# MAIN.net
KiCad netlist of a schematic drawn in Altium Designer
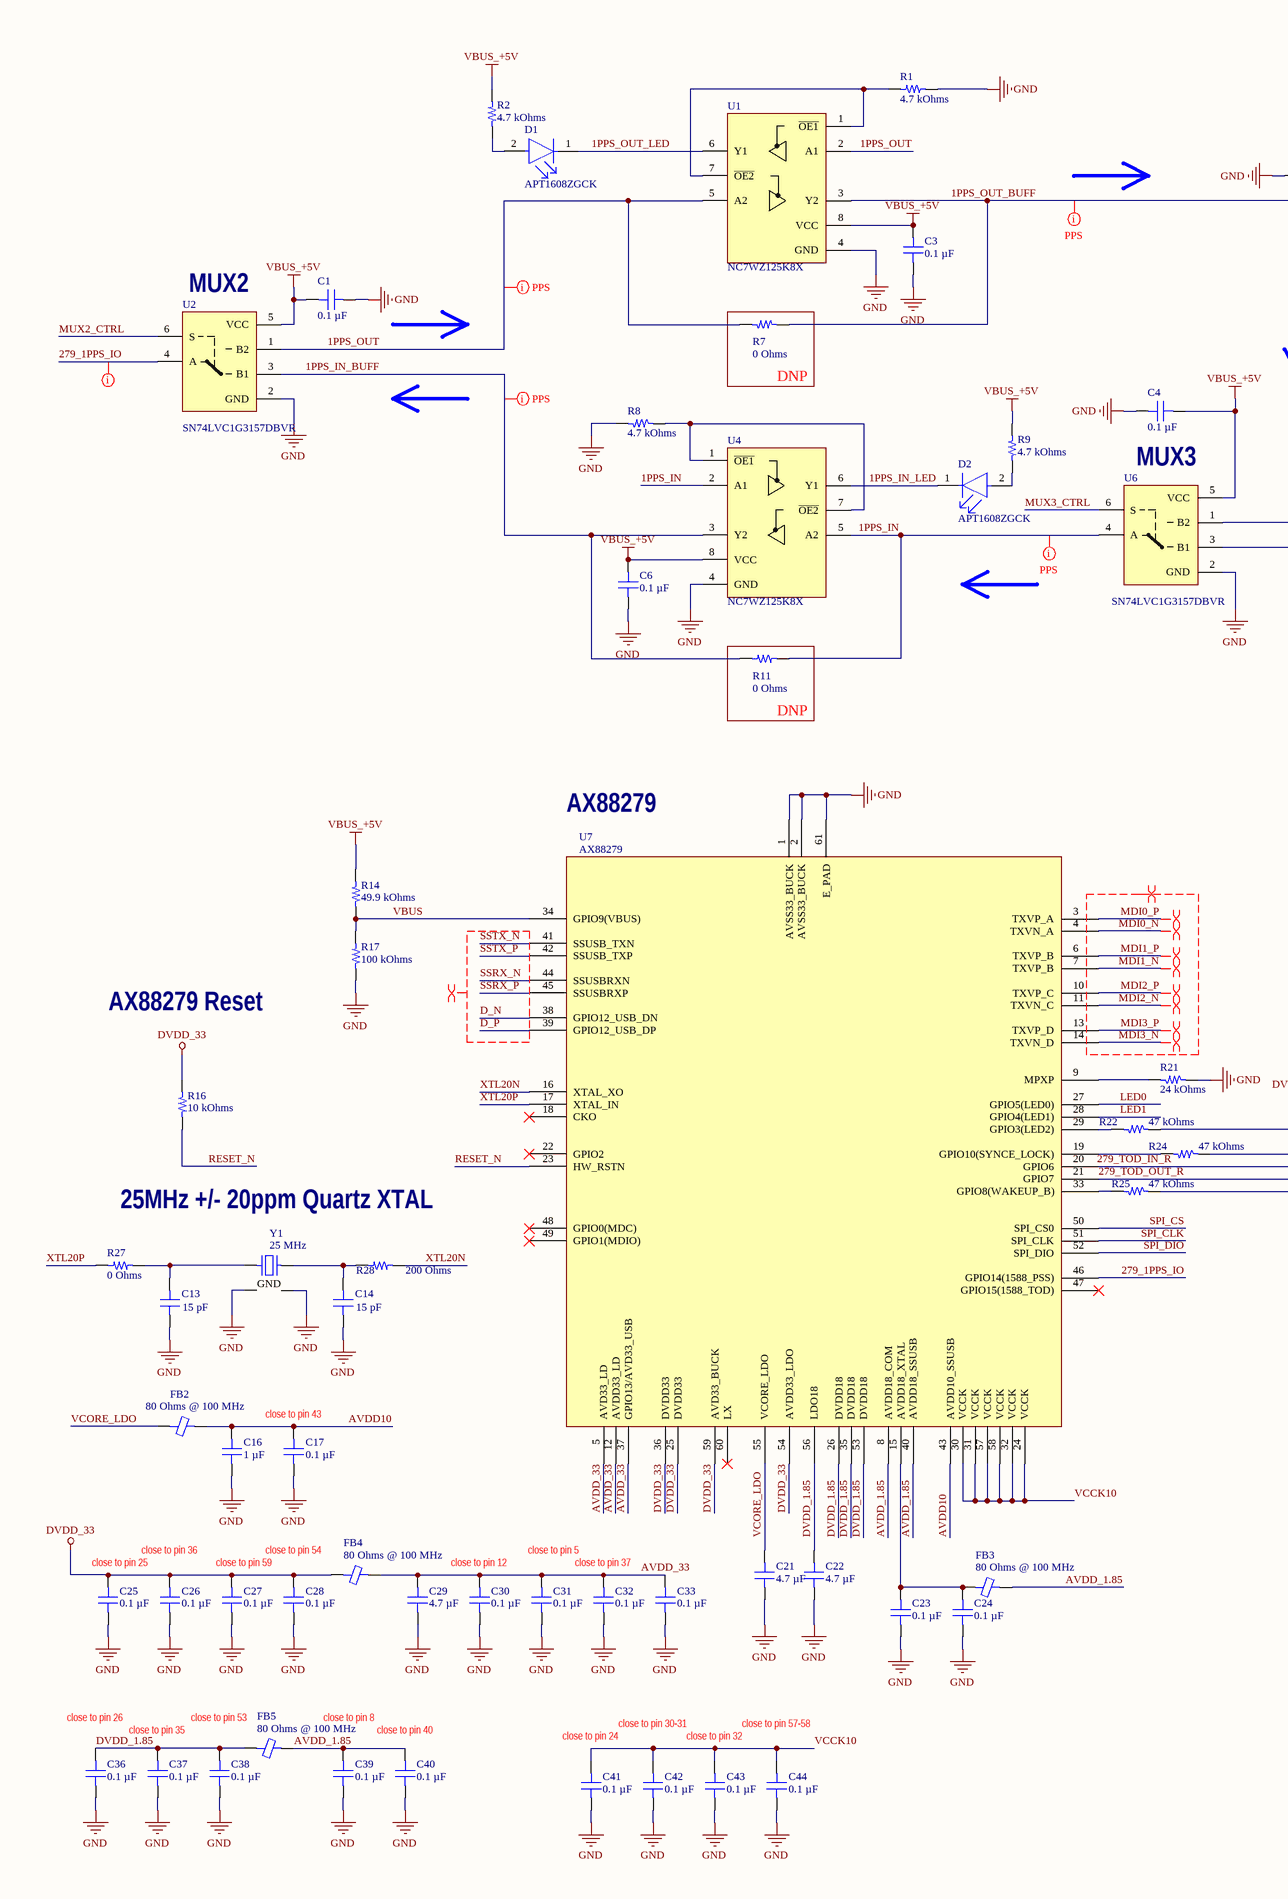
[diagram p0: MAIN.SchDoc, left]
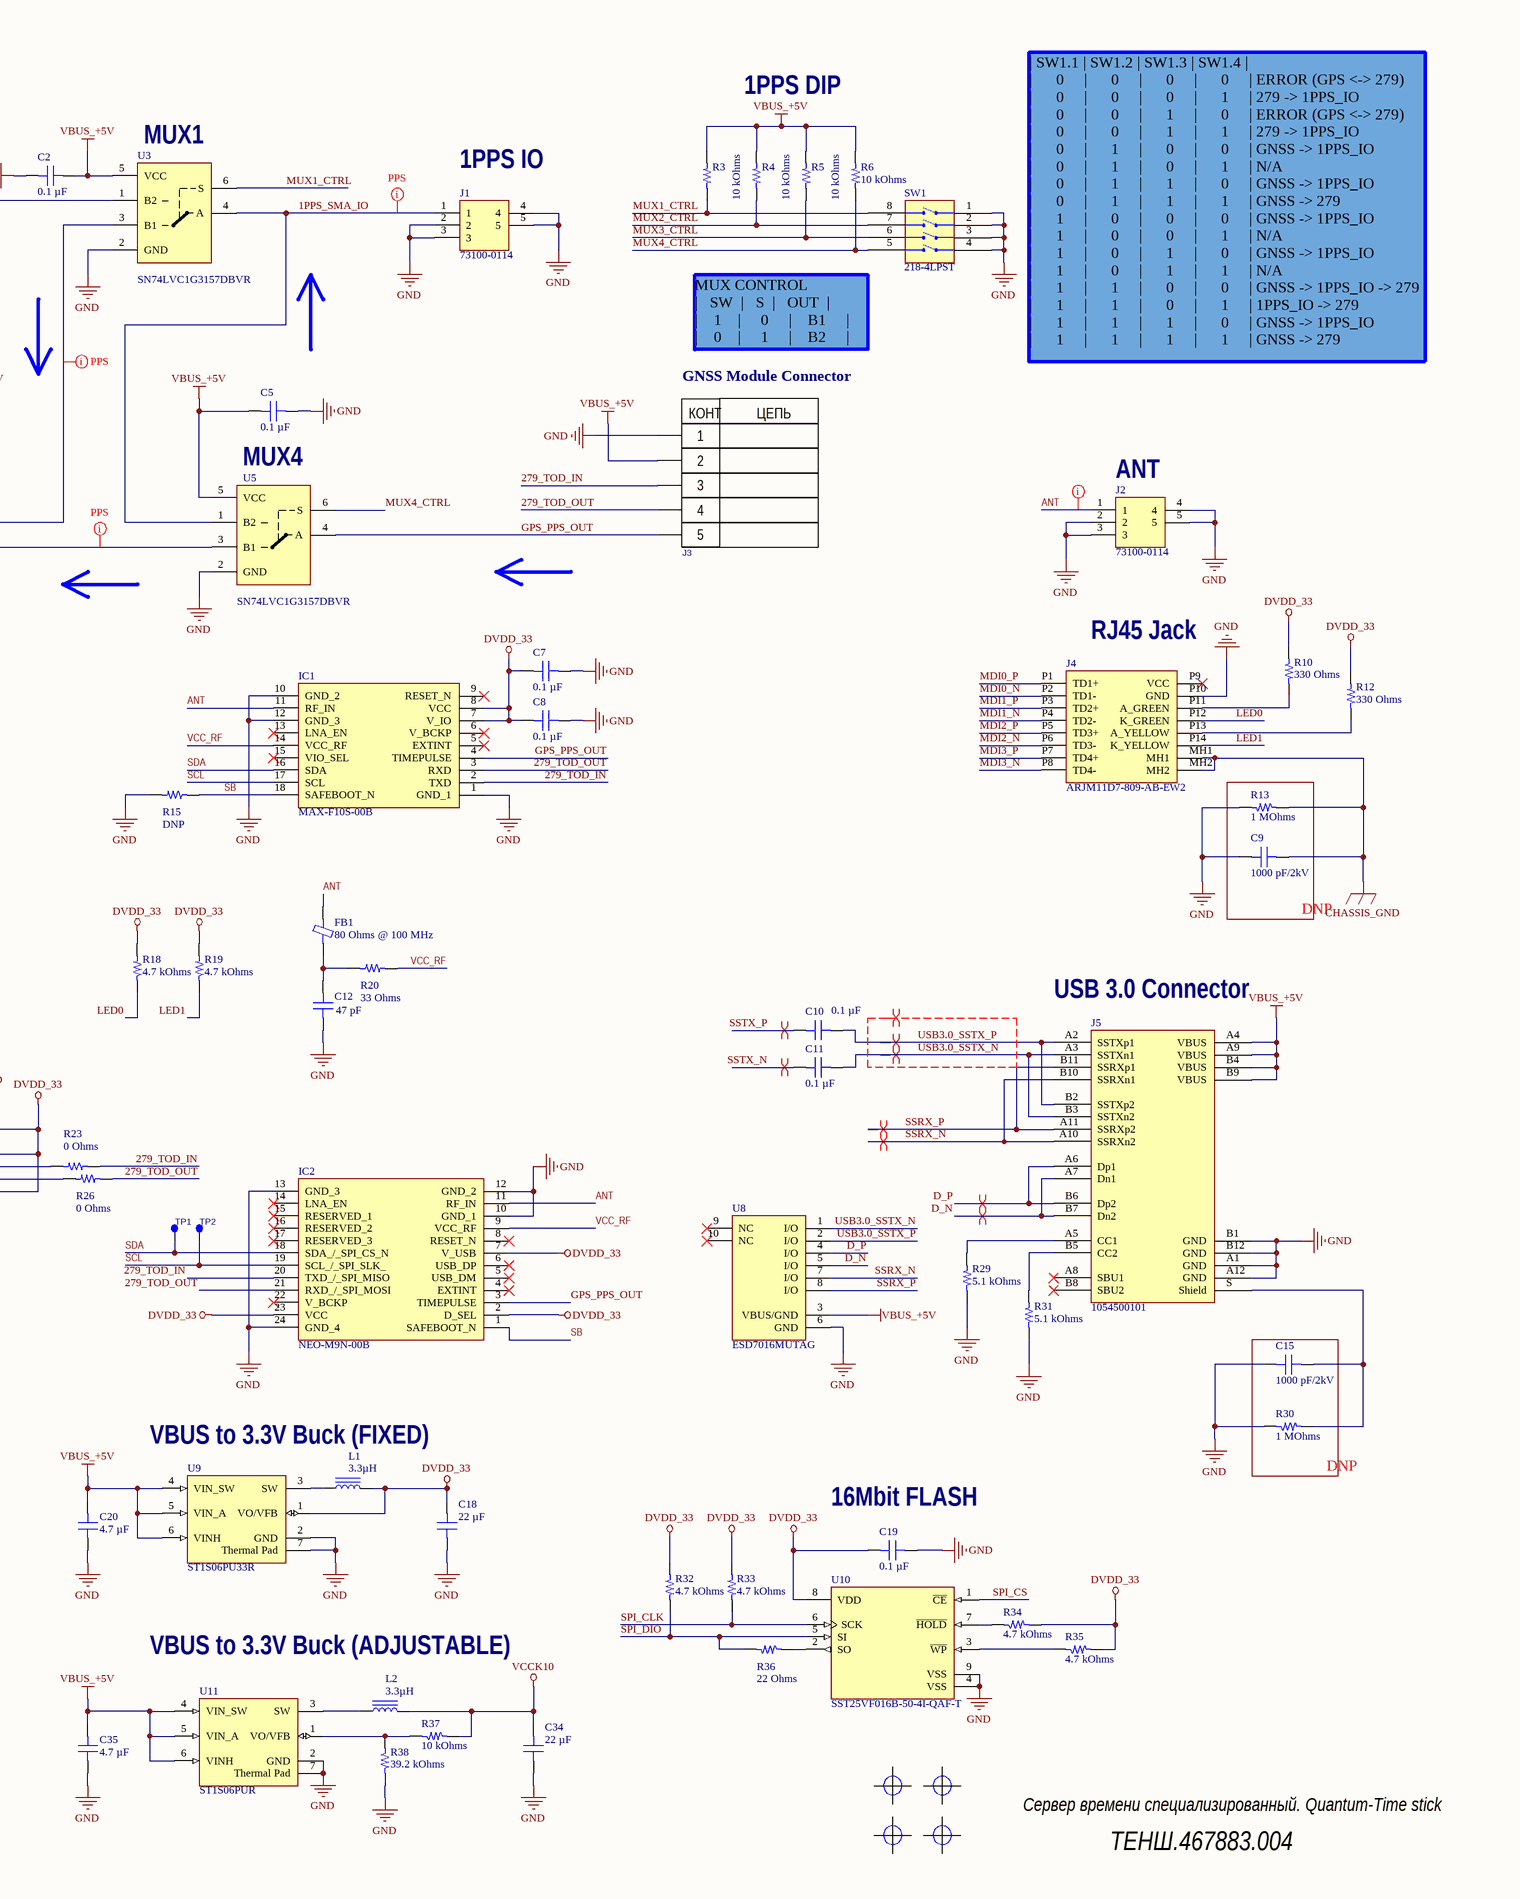
[diagram p1: MAIN.SchDoc, right]

(export (version "E")
  (design (tool "Eeschema 10.0.6"))
  (components
    (comp (ref "C1")
      (value "0.1 µF")
      (footprint "CAP 0402_1005")
      (description "CAP CER 0.1UF 10V X7R 0402")
      (fields (field (name "TOLERANCE") "±10%") (field (name "MANUFACTURER") "Yageo"))
      (libsource (lib "Celestial Altium Library - altium_library") (part "Capacitor"))
    )
    (comp (ref "C2")
      (value "0.1 µF")
      (footprint "CAP 0402_1005")
      (description "CAP CER 0.1UF 10V X7R 0402")
      (fields (field (name "TOLERANCE") "±10%") (field (name "MANUFACTURER") "Yageo"))
      (libsource (lib "Celestial Altium Library - altium_library") (part "Capacitor"))
    )
    (comp (ref "C3")
      (value "0.1 µF")
      (footprint "CAP 0402_1005")
      (description "CAP CER 0.1UF 10V X7R 0402")
      (fields (field (name "TOLERANCE") "±10%") (field (name "MANUFACTURER") "Yageo"))
      (libsource (lib "Celestial Altium Library - altium_library") (part "Capacitor"))
    )
    (comp (ref "C4")
      (value "0.1 µF")
      (footprint "CAP 0402_1005")
      (description "CAP CER 0.1UF 10V X7R 0402")
      (fields (field (name "TOLERANCE") "±10%") (field (name "MANUFACTURER") "Yageo"))
      (libsource (lib "Celestial Altium Library - altium_library") (part "Capacitor"))
    )
    (comp (ref "C5")
      (value "0.1 µF")
      (footprint "CAP 0402_1005")
      (description "CAP CER 0.1UF 10V X7R 0402")
      (fields (field (name "TOLERANCE") "±10%") (field (name "MANUFACTURER") "Yageo"))
      (libsource (lib "Celestial Altium Library - altium_library") (part "Capacitor"))
    )
    (comp (ref "C6")
      (value "0.1 µF")
      (footprint "CAP 0402_1005")
      (description "CAP CER 0.1UF 10V X7R 0402")
      (fields (field (name "TOLERANCE") "±10%") (field (name "MANUFACTURER") "Yageo"))
      (libsource (lib "Celestial Altium Library - altium_library") (part "Capacitor"))
    )
    (comp (ref "C7")
      (value "0.1 µF")
      (footprint "CAP 0402_1005")
      (description "CAP CER 0.1UF 10V X7R 0402")
      (fields (field (name "TOLERANCE") "±10%") (field (name "MANUFACTURER") "Yageo"))
      (libsource (lib "Celestial Altium Library - altium_library") (part "Capacitor"))
    )
    (comp (ref "C8")
      (value "0.1 µF")
      (footprint "CAP 0402_1005")
      (description "CAP CER 0.1UF 10V X7R 0402")
      (fields (field (name "TOLERANCE") "±10%") (field (name "MANUFACTURER") "Yageo"))
      (libsource (lib "Celestial Altium Library - altium_library") (part "Capacitor"))
    )
    (comp (ref "C9")
      (value "1000 pF/2kV")
      (footprint "CAP 1206_3216 - 0.8MM")
      (description "CAP CER 1000PF 2KV X7R 1206")
      (fields (field (name "PART NUMBER") "CC1206KKX7RDBB102") (field (name "MANUFACTURER") "Yageo"))
      (libsource (lib "Celestial Altium Library - altium_library") (part "Capacitor"))
    )
    (comp (ref "C10")
      (value "0.1 µF")
      (footprint "CAP 0402_1005")
      (description "CAP CER 0.1UF 10V X7R 0402")
      (fields (field (name "TOLERANCE") "±10%") (field (name "MANUFACTURER") "Yageo"))
      (libsource (lib "Celestial Altium Library - altium_library") (part "Capacitor"))
    )
    (comp (ref "C11")
      (value "0.1 µF")
      (footprint "CAP 0402_1005")
      (description "CAP CER 0.1UF 10V X7R 0402")
      (fields (field (name "TOLERANCE") "±10%") (field (name "MANUFACTURER") "Yageo"))
      (libsource (lib "Celestial Altium Library - altium_library") (part "Capacitor"))
    )
    (comp (ref "C12")
      (value "47 pF")
      (footprint "CAP 0402_1005")
      (description "CAP CER 47PF 50V C0G/NPO 0402")
      (fields (field (name "MANUFACTURER") "Yageo") (field (name "TOLERANCE") "±10%"))
      (libsource (lib "Celestial Altium Library - altium_library") (part "Capacitor"))
    )
    (comp (ref "C13")
      (value "15 pF")
      (footprint "CAP 0402_1005")
      (description "CAP CER 15PF 50V C0G/NPO 0402")
      (fields (field (name "MANUFACTURER") "Yageo") (field (name "TOLERANCE") "±10%"))
      (libsource (lib "Celestial Altium Library - altium_library") (part "Capacitor"))
    )
    (comp (ref "C14")
      (value "15 pF")
      (footprint "CAP 0402_1005")
      (description "CAP CER 15PF 50V C0G/NPO 0402")
      (fields (field (name "MANUFACTURER") "Yageo") (field (name "TOLERANCE") "±10%"))
      (libsource (lib "Celestial Altium Library - altium_library") (part "Capacitor"))
    )
    (comp (ref "C15")
      (value "1000 pF/2kV")
      (footprint "CAP 1206_3216 - 0.8MM")
      (description "CAP CER 1000PF 2KV X7R 1206")
      (fields (field (name "PART NUMBER") "CC1206KKX7RDBB102") (field (name "MANUFACTURER") "Yageo"))
      (libsource (lib "Celestial Altium Library - altium_library") (part "Capacitor"))
    )
    (comp (ref "C16")
      (value "1 µF")
      (footprint "CAP 0402_1005")
      (description "CAP CER 1UF 10V X5R 0402")
      (fields (field (name "TOLERANCE") "±10%") (field (name "MANUFACTURER") "Yageo"))
      (libsource (lib "Celestial Altium Library - altium_library") (part "Capacitor"))
    )
    (comp (ref "C17")
      (value "0.1 µF")
      (footprint "CAP 0402_1005")
      (description "CAP CER 0.1UF 10V X7R 0402")
      (fields (field (name "TOLERANCE") "±10%") (field (name "MANUFACTURER") "Yageo"))
      (libsource (lib "Celestial Altium Library - altium_library") (part "Capacitor"))
    )
    (comp (ref "C18")
      (value "22 µF")
      (footprint "CAP 0603_1608")
      (description "CAP CER 22UF 10V X5R 0603")
      (fields (field (name "MANUFACTURER") "Yageo") (field (name "TOLERANCE") "±20%"))
      (libsource (lib "Celestial Altium Library - altium_library") (part "Capacitor"))
    )
    (comp (ref "C19")
      (value "0.1 µF")
      (footprint "CAP 0402_1005")
      (description "CAP CER 0.1UF 10V X7R 0402")
      (fields (field (name "TOLERANCE") "±10%") (field (name "MANUFACTURER") "Yageo"))
      (libsource (lib "Celestial Altium Library - altium_library") (part "Capacitor"))
    )
    (comp (ref "C20")
      (value "4.7 µF")
      (footprint "CAP 0402_1005")
      (description "CAP CER 4.7UF 10V X5R 0402")
      (fields (field (name "TOLERANCE") "±20%") (field (name "MANUFACTURER") "Yageo"))
      (libsource (lib "Celestial Altium Library - altium_library") (part "Capacitor"))
    )
    (comp (ref "C21")
      (value "4.7 µF")
      (footprint "CAP 0402_1005")
      (description "CAP CER 4.7UF 10V X5R 0402")
      (fields (field (name "TOLERANCE") "±20%") (field (name "MANUFACTURER") "Yageo"))
      (libsource (lib "Celestial Altium Library - altium_library") (part "Capacitor"))
    )
    (comp (ref "C22")
      (value "4.7 µF")
      (footprint "CAP 0402_1005")
      (description "CAP CER 4.7UF 10V X5R 0402")
      (fields (field (name "TOLERANCE") "±20%") (field (name "MANUFACTURER") "Yageo"))
      (libsource (lib "Celestial Altium Library - altium_library") (part "Capacitor"))
    )
    (comp (ref "C23")
      (value "0.1 µF")
      (footprint "CAP 0402_1005")
      (description "CAP CER 0.1UF 10V X7R 0402")
      (fields (field (name "TOLERANCE") "±10%") (field (name "MANUFACTURER") "Yageo"))
      (libsource (lib "Celestial Altium Library - altium_library") (part "Capacitor"))
    )
    (comp (ref "C24")
      (value "0.1 µF")
      (footprint "CAP 0402_1005")
      (description "CAP CER 0.1UF 10V X7R 0402")
      (fields (field (name "TOLERANCE") "±10%") (field (name "MANUFACTURER") "Yageo"))
      (libsource (lib "Celestial Altium Library - altium_library") (part "Capacitor"))
    )
    (comp (ref "C25")
      (value "0.1 µF")
      (footprint "CAP 0402_1005")
      (description "CAP CER 0.1UF 10V X7R 0402")
      (fields (field (name "TOLERANCE") "±10%") (field (name "MANUFACTURER") "Yageo"))
      (libsource (lib "Celestial Altium Library - altium_library") (part "Capacitor"))
    )
    (comp (ref "C26")
      (value "0.1 µF")
      (footprint "CAP 0402_1005")
      (description "CAP CER 0.1UF 10V X7R 0402")
      (fields (field (name "TOLERANCE") "±10%") (field (name "MANUFACTURER") "Yageo"))
      (libsource (lib "Celestial Altium Library - altium_library") (part "Capacitor"))
    )
    (comp (ref "C27")
      (value "0.1 µF")
      (footprint "CAP 0402_1005")
      (description "CAP CER 0.1UF 10V X7R 0402")
      (fields (field (name "TOLERANCE") "±10%") (field (name "MANUFACTURER") "Yageo"))
      (libsource (lib "Celestial Altium Library - altium_library") (part "Capacitor"))
    )
    (comp (ref "C28")
      (value "0.1 µF")
      (footprint "CAP 0402_1005")
      (description "CAP CER 0.1UF 10V X7R 0402")
      (fields (field (name "TOLERANCE") "±10%") (field (name "MANUFACTURER") "Yageo"))
      (libsource (lib "Celestial Altium Library - altium_library") (part "Capacitor"))
    )
    (comp (ref "C29")
      (value "4.7 µF")
      (footprint "CAP 0402_1005")
      (description "CAP CER 4.7UF 10V X5R 0402")
      (fields (field (name "TOLERANCE") "±20%") (field (name "MANUFACTURER") "Yageo"))
      (libsource (lib "Celestial Altium Library - altium_library") (part "Capacitor"))
    )
    (comp (ref "C30")
      (value "0.1 µF")
      (footprint "CAP 0402_1005")
      (description "CAP CER 0.1UF 10V X7R 0402")
      (fields (field (name "TOLERANCE") "±10%") (field (name "MANUFACTURER") "Yageo"))
      (libsource (lib "Celestial Altium Library - altium_library") (part "Capacitor"))
    )
    (comp (ref "C31")
      (value "0.1 µF")
      (footprint "CAP 0402_1005")
      (description "CAP CER 0.1UF 10V X7R 0402")
      (fields (field (name "TOLERANCE") "±10%") (field (name "MANUFACTURER") "Yageo"))
      (libsource (lib "Celestial Altium Library - altium_library") (part "Capacitor"))
    )
    (comp (ref "C32")
      (value "0.1 µF")
      (footprint "CAP 0402_1005")
      (description "CAP CER 0.1UF 10V X7R 0402")
      (fields (field (name "TOLERANCE") "±10%") (field (name "MANUFACTURER") "Yageo"))
      (libsource (lib "Celestial Altium Library - altium_library") (part "Capacitor"))
    )
    (comp (ref "C33")
      (value "0.1 µF")
      (footprint "CAP 0402_1005")
      (description "CAP CER 0.1UF 10V X7R 0402")
      (fields (field (name "TOLERANCE") "±10%") (field (name "MANUFACTURER") "Yageo"))
      (libsource (lib "Celestial Altium Library - altium_library") (part "Capacitor"))
    )
    (comp (ref "C34")
      (value "22 µF")
      (footprint "CAP 0603_1608")
      (description "CAP CER 22UF 10V X5R 0603")
      (fields (field (name "MANUFACTURER") "Yageo") (field (name "TOLERANCE") "±20%"))
      (libsource (lib "Celestial Altium Library - altium_library") (part "Capacitor"))
    )
    (comp (ref "C35")
      (value "4.7 µF")
      (footprint "CAP 0402_1005")
      (description "CAP CER 4.7UF 10V X5R 0402")
      (fields (field (name "TOLERANCE") "±20%") (field (name "MANUFACTURER") "Yageo"))
      (libsource (lib "Celestial Altium Library - altium_library") (part "Capacitor"))
    )
    (comp (ref "C36")
      (value "0.1 µF")
      (footprint "CAP 0402_1005")
      (description "CAP CER 0.1UF 10V X7R 0402")
      (fields (field (name "TOLERANCE") "±10%") (field (name "MANUFACTURER") "Yageo"))
      (libsource (lib "Celestial Altium Library - altium_library") (part "Capacitor"))
    )
    (comp (ref "C37")
      (value "0.1 µF")
      (footprint "CAP 0402_1005")
      (description "CAP CER 0.1UF 10V X7R 0402")
      (fields (field (name "TOLERANCE") "±10%") (field (name "MANUFACTURER") "Yageo"))
      (libsource (lib "Celestial Altium Library - altium_library") (part "Capacitor"))
    )
    (comp (ref "C38")
      (value "0.1 µF")
      (footprint "CAP 0402_1005")
      (description "CAP CER 0.1UF 10V X7R 0402")
      (fields (field (name "TOLERANCE") "±10%") (field (name "MANUFACTURER") "Yageo"))
      (libsource (lib "Celestial Altium Library - altium_library") (part "Capacitor"))
    )
    (comp (ref "C39")
      (value "0.1 µF")
      (footprint "CAP 0402_1005")
      (description "CAP CER 0.1UF 10V X7R 0402")
      (fields (field (name "TOLERANCE") "±10%") (field (name "MANUFACTURER") "Yageo"))
      (libsource (lib "Celestial Altium Library - altium_library") (part "Capacitor"))
    )
    (comp (ref "C40")
      (value "0.1 µF")
      (footprint "CAP 0402_1005")
      (description "CAP CER 0.1UF 10V X7R 0402")
      (fields (field (name "TOLERANCE") "±10%") (field (name "MANUFACTURER") "Yageo"))
      (libsource (lib "Celestial Altium Library - altium_library") (part "Capacitor"))
    )
    (comp (ref "C41")
      (value "0.1 µF")
      (footprint "CAP 0402_1005")
      (description "CAP CER 0.1UF 10V X7R 0402")
      (fields (field (name "TOLERANCE") "±10%") (field (name "MANUFACTURER") "Yageo"))
      (libsource (lib "Celestial Altium Library - altium_library") (part "Capacitor"))
    )
    (comp (ref "C42")
      (value "0.1 µF")
      (footprint "CAP 0402_1005")
      (description "CAP CER 0.1UF 10V X7R 0402")
      (fields (field (name "TOLERANCE") "±10%") (field (name "MANUFACTURER") "Yageo"))
      (libsource (lib "Celestial Altium Library - altium_library") (part "Capacitor"))
    )
    (comp (ref "C43")
      (value "0.1 µF")
      (footprint "CAP 0402_1005")
      (description "CAP CER 0.1UF 10V X7R 0402")
      (fields (field (name "TOLERANCE") "±10%") (field (name "MANUFACTURER") "Yageo"))
      (libsource (lib "Celestial Altium Library - altium_library") (part "Capacitor"))
    )
    (comp (ref "C44")
      (value "0.1 µF")
      (footprint "CAP 0402_1005")
      (description "CAP CER 0.1UF 10V X7R 0402")
      (fields (field (name "TOLERANCE") "±10%") (field (name "MANUFACTURER") "Yageo"))
      (libsource (lib "Celestial Altium Library - altium_library") (part "Capacitor"))
    )
    (comp (ref "D1")
      (value "APT1608ZGCK")
      (footprint "FP-APT1608ZGCK-MFG")
      (description "LED GREEN CLEAR CHIP SMD")
      (fields (field (name "MANUFACTURER") "Kingbright"))
      (libsource (lib "Altium Content Vault") (part "8706943c75ba83719d021d2fdc84c58"))
    )
    (comp (ref "D2")
      (value "APT1608ZGCK")
      (footprint "FP-APT1608ZGCK-MFG")
      (description "LED GREEN CLEAR CHIP SMD")
      (fields (field (name "MANUFACTURER") "Kingbright"))
      (libsource (lib "Altium Content Vault") (part "8706943c75ba83719d021d2fdc84c58"))
    )
    (comp (ref "FB1")
      (value "80 Ohms @ 100 MHz")
      (footprint "FER 0402_1005")
      (description "FERRITE BEAD 80 OHM 0402 1LN")
      (fields
        (field (name "MANUFACTURER") "Murata Electronics")
        (field (name "PART NUMBER") "BLM15PD800SN1D")
      )
      (libsource (lib "Celestial Altium Library - altium_library") (part "Ferrite Chip"))
    )
    (comp (ref "FB2")
      (value "80 Ohms @ 100 MHz")
      (footprint "FER 0402_1005")
      (description "FERRITE BEAD 80 OHM 0402 1LN")
      (fields
        (field (name "MANUFACTURER") "Murata Electronics")
        (field (name "PART NUMBER") "BLM15PD800SN1D")
      )
      (libsource (lib "Celestial Altium Library - altium_library") (part "Ferrite Chip"))
    )
    (comp (ref "FB3")
      (value "80 Ohms @ 100 MHz")
      (footprint "FER 0402_1005")
      (description "FERRITE BEAD 80 OHM 0402 1LN")
      (fields
        (field (name "MANUFACTURER") "Murata Electronics")
        (field (name "PART NUMBER") "BLM15PD800SN1D")
      )
      (libsource (lib "Celestial Altium Library - altium_library") (part "Ferrite Chip"))
    )
    (comp (ref "FB4")
      (value "80 Ohms @ 100 MHz")
      (footprint "FER 0402_1005")
      (description "FERRITE BEAD 80 OHM 0402 1LN")
      (fields
        (field (name "MANUFACTURER") "Murata Electronics")
        (field (name "PART NUMBER") "BLM15PD800SN1D")
      )
      (libsource (lib "Celestial Altium Library - altium_library") (part "Ferrite Chip"))
    )
    (comp (ref "FB5")
      (value "80 Ohms @ 100 MHz")
      (footprint "FER 0402_1005")
      (description "FERRITE BEAD 80 OHM 0402 1LN")
      (fields
        (field (name "MANUFACTURER") "Murata Electronics")
        (field (name "PART NUMBER") "BLM15PD800SN1D")
      )
      (libsource (lib "Celestial Altium Library - altium_library") (part "Ferrite Chip"))
    )
    (comp (ref "IC1")
      (value "MAX-F10S-00B")
      (footprint "SamacSys:MAXF10S00B")
      (description "Integrated Circuit")
      (libsource (lib "SamacSys") (part "MAX-F10S-00B"))
    )
    (comp (ref "IC2")
      (value "NEO-M9N-00B")
      (footprint "SamacSys:NEOM9N00B")
      (description "Integrated Circuit")
      (fields (field (name "MOUSER PART NUMBER") "377-NEO-M9N-00B"))
      (libsource (lib "SamacSys") (part "NEO-M9N-00B"))
    )
    (comp (ref "J1")
      (value "73100-0114")
      (footprint "SamacSys:731000114")
      (description "Connector")
      (fields (field (name "MOUSER PART NUMBER") "538-73100-0114"))
      (libsource (lib "SamacSys") (part "73100-0114"))
    )
    (comp (ref "J2")
      (value "73100-0114")
      (footprint "SamacSys:731000114")
      (description "Connector")
      (fields (field (name "MOUSER PART NUMBER") "538-73100-0114"))
      (libsource (lib "SamacSys") (part "73100-0114"))
    )
    (comp (ref "J3")
      (value "PBS-5")
      (footprint "SamacSys:PBS-5")
      (description "Connector")
      (fields (field (name "MANUFACTURER") "Connfly") (field (name "PART NUMBER") "PBD-5"))
      (libsource (lib "SamacSys") (part "PBS-5"))
    )
    (comp (ref "J4")
      (value "ARJM11D7-809-AB-EW2")
      (footprint "SamacSys:ARJM11D7809ABEW2")
      (description "Connector")
      (fields (field (name "MOUSER PART NUMBER") "815-RJM11D7809ABEW2"))
      (libsource (lib "*") (part "ARJM11D7-809-AB-EW2"))
    )
    (comp (ref "J5")
      (value "1054500101")
      (footprint "Molex 1054500101")
      (description "CONN RCP USB3.1 TYPEC 24P SMD RA")
      (fields (field (name "MANUFACTURER") "Molex"))
      (libsource (lib "Celestial Altium Library - altium_library") (part "USB 3.0 Type C"))
    )
    (comp (ref "L1")
      (value "3.3µH")
      (footprint "IND 1008_2520")
      (description "FIXED IND 3.3UH 1.2A 100 MOHM")
      (fields (field (name "TOLERANCE") "±20%") (field (name "MANUFACTURER") "Murata Electronics"))
      (libsource (lib "Celestial Altium Library - altium_library") (part "Inductor"))
    )
    (comp (ref "L2")
      (value "3.3µH")
      (footprint "IND 1008_2520")
      (description "FIXED IND 3.3UH 1.2A 100 MOHM")
      (fields (field (name "TOLERANCE") "±20%") (field (name "MANUFACTURER") "Murata Electronics"))
      (libsource (lib "Celestial Altium Library - altium_library") (part "Inductor"))
    )
    (comp (ref "MNT1")
      (value "MOUNT_HOLE")
      (footprint "SamacSys:MOUNT_3mm")
      (description "Mount hole")
      (libsource (lib "SamacSys") (part "MOUNT_HOLE"))
    )
    (comp (ref "MNT2")
      (value "MOUNT_HOLE")
      (footprint "SamacSys:MOUNT_3mm")
      (description "Mount hole")
      (libsource (lib "SamacSys") (part "MOUNT_HOLE"))
    )
    (comp (ref "MNT3")
      (value "MOUNT_HOLE")
      (footprint "SamacSys:MOUNT_3mm")
      (description "Mount hole")
      (libsource (lib "SamacSys") (part "MOUNT_HOLE"))
    )
    (comp (ref "MNT4")
      (value "MOUNT_HOLE")
      (footprint "SamacSys:MOUNT_3mm")
      (description "Mount hole")
      (libsource (lib "SamacSys") (part "MOUNT_HOLE"))
    )
    (comp (ref "R1")
      (value "4.7 kOhms")
      (footprint "YAGEO RES 0402_1005")
      (description "RES 4.7K OHM 1% 1/16W 0402")
      (fields (field (name "TOLERANCE") "±1%") (field (name "MANUFACTURER") "Yageo"))
      (libsource (lib "Celestial Altium Library - altium_library") (part "Resistor"))
    )
    (comp (ref "R2")
      (value "4.7 kOhms")
      (footprint "YAGEO RES 0402_1005")
      (description "RES 4.7K OHM 1% 1/16W 0402")
      (fields (field (name "TOLERANCE") "±1%") (field (name "MANUFACTURER") "Yageo"))
      (libsource (lib "Celestial Altium Library - altium_library") (part "Resistor"))
    )
    (comp (ref "R3")
      (value "10 kOhms")
      (footprint "YAGEO RES 0402_1005")
      (description "RES 10K OHM 1% 1/16W 0402")
      (fields (field (name "TOLERANCE") "±1%") (field (name "MANUFACTURER") "Yageo"))
      (libsource (lib "Celestial Altium Library - altium_library") (part "Resistor"))
    )
    (comp (ref "R4")
      (value "10 kOhms")
      (footprint "YAGEO RES 0402_1005")
      (description "RES 10K OHM 1% 1/16W 0402")
      (fields (field (name "TOLERANCE") "±1%") (field (name "MANUFACTURER") "Yageo"))
      (libsource (lib "Celestial Altium Library - altium_library") (part "Resistor"))
    )
    (comp (ref "R5")
      (value "10 kOhms")
      (footprint "YAGEO RES 0402_1005")
      (description "RES 10K OHM 1% 1/16W 0402")
      (fields (field (name "TOLERANCE") "±1%") (field (name "MANUFACTURER") "Yageo"))
      (libsource (lib "Celestial Altium Library - altium_library") (part "Resistor"))
    )
    (comp (ref "R6")
      (value "10 kOhms")
      (footprint "YAGEO RES 0402_1005")
      (description "RES 10K OHM 1% 1/16W 0402")
      (fields (field (name "TOLERANCE") "±1%") (field (name "MANUFACTURER") "Yageo"))
      (libsource (lib "Celestial Altium Library - altium_library") (part "Resistor"))
    )
    (comp (ref "R7")
      (value "0 Ohms")
      (footprint "YAGEO RES 0402_1005")
      (description "RES 0 OHM JUMPER 1/16W 0402")
      (fields (field (name "TOLERANCE") "Jumper") (field (name "MANUFACTURER") "Yageo"))
      (libsource (lib "Celestial Altium Library - altium_library") (part "Resistor"))
    )
    (comp (ref "R8")
      (value "4.7 kOhms")
      (footprint "YAGEO RES 0402_1005")
      (description "RES 4.7K OHM 1% 1/16W 0402")
      (fields (field (name "TOLERANCE") "±1%") (field (name "MANUFACTURER") "Yageo"))
      (libsource (lib "Celestial Altium Library - altium_library") (part "Resistor"))
    )
    (comp (ref "R9")
      (value "4.7 kOhms")
      (footprint "YAGEO RES 0402_1005")
      (description "RES 4.7K OHM 1% 1/16W 0402")
      (fields (field (name "TOLERANCE") "±1%") (field (name "MANUFACTURER") "Yageo"))
      (libsource (lib "Celestial Altium Library - altium_library") (part "Resistor"))
    )
    (comp (ref "R10")
      (value "330 Ohms")
      (footprint "YAGEO RES 0402_1005")
      (description "RES 330 OHM 1% 1/16W 0402")
      (fields (field (name "TOLERANCE") "±1%") (field (name "MANUFACTURER") "Yageo"))
      (libsource (lib "Celestial Altium Library - altium_library") (part "Resistor"))
    )
    (comp (ref "R11")
      (value "0 Ohms")
      (footprint "YAGEO RES 0402_1005")
      (description "RES 0 OHM JUMPER 1/16W 0402")
      (fields (field (name "TOLERANCE") "Jumper") (field (name "MANUFACTURER") "Yageo"))
      (libsource (lib "Celestial Altium Library - altium_library") (part "Resistor"))
    )
    (comp (ref "R12")
      (value "330 Ohms")
      (footprint "YAGEO RES 0402_1005")
      (description "RES 330 OHM 1% 1/16W 0402")
      (fields (field (name "TOLERANCE") "±1%") (field (name "MANUFACTURER") "Yageo"))
      (libsource (lib "Celestial Altium Library - altium_library") (part "Resistor"))
    )
    (comp (ref "R13")
      (value "1 MOhms")
      (footprint "YAGEO RES 0402_1005")
      (description "RES 1M OHM 1% 1/16W 0402")
      (fields (field (name "TOLERANCE") "±1%") (field (name "MANUFACTURER") "Yageo"))
      (libsource (lib "Celestial Altium Library - altium_library") (part "Resistor"))
    )
    (comp (ref "R14")
      (value "49.9 kOhms")
      (footprint "YAGEO RES 0402_1005")
      (description "RES 49.9K OHM 1% 1/16W 0402")
      (fields (field (name "TOLERANCE") "±1%") (field (name "MANUFACTURER") "Yageo"))
      (libsource (lib "Celestial Altium Library - altium_library") (part "Resistor"))
    )
    (comp (ref "R15")
      (value "DNP")
      (footprint "YAGEO RES 0402_1005")
      (description "RES 0 OHM JUMPER 1/16W 0402")
      (fields (field (name "TOLERANCE") "Jumper") (field (name "MANUFACTURER") "Yageo"))
      (libsource (lib "Celestial Altium Library - altium_library") (part "Resistor"))
    )
    (comp (ref "R16")
      (value "10 kOhms")
      (footprint "YAGEO RES 0402_1005")
      (description "RES 10K OHM 1% 1/16W 0402")
      (fields (field (name "TOLERANCE") "±1%") (field (name "MANUFACTURER") "Yageo"))
      (libsource (lib "Celestial Altium Library - altium_library") (part "Resistor"))
    )
    (comp (ref "R17")
      (value "100 kOhms")
      (footprint "YAGEO RES 0402_1005")
      (description "RES 100K OHM 1% 1/16W 0402")
      (fields (field (name "TOLERANCE") "±1%") (field (name "MANUFACTURER") "Yageo"))
      (libsource (lib "Celestial Altium Library - altium_library") (part "Resistor"))
    )
    (comp (ref "R18")
      (value "4.7 kOhms")
      (footprint "YAGEO RES 0402_1005")
      (description "RES 4.7K OHM 1% 1/16W 0402")
      (fields (field (name "TOLERANCE") "±1%") (field (name "MANUFACTURER") "Yageo"))
      (libsource (lib "Celestial Altium Library - altium_library") (part "Resistor"))
    )
    (comp (ref "R19")
      (value "4.7 kOhms")
      (footprint "YAGEO RES 0402_1005")
      (description "RES 4.7K OHM 1% 1/16W 0402")
      (fields (field (name "TOLERANCE") "±1%") (field (name "MANUFACTURER") "Yageo"))
      (libsource (lib "Celestial Altium Library - altium_library") (part "Resistor"))
    )
    (comp (ref "R20")
      (value "33 Ohms")
      (footprint "YAGEO RES 0402_1005")
      (description "RES 33 OHM 1% 1/16W 0402")
      (fields (field (name "TOLERANCE") "±1%") (field (name "MANUFACTURER") "Yageo"))
      (libsource (lib "Celestial Altium Library - altium_library") (part "Resistor"))
    )
    (comp (ref "R21")
      (value "24 kOhms")
      (footprint "YAGEO RES 0402_1005")
      (description "RES 24K OHM 1% 1/16W 0402")
      (fields (field (name "TOLERANCE") "±1%") (field (name "MANUFACTURER") "Yageo"))
      (libsource (lib "Celestial Altium Library - altium_library") (part "Resistor"))
    )
    (comp (ref "R22")
      (value "47 kOhms")
      (footprint "YAGEO RES 0402_1005")
      (description "RES 47K OHM 1% 1/16W 0402")
      (fields (field (name "TOLERANCE") "±1%") (field (name "MANUFACTURER") "Yageo"))
      (libsource (lib "Celestial Altium Library - altium_library") (part "Resistor"))
    )
    (comp (ref "R23")
      (value "0 Ohms")
      (footprint "YAGEO RES 0402_1005")
      (description "RES 0 OHM JUMPER 1/16W 0402")
      (fields (field (name "TOLERANCE") "Jumper") (field (name "MANUFACTURER") "Yageo"))
      (libsource (lib "Celestial Altium Library - altium_library") (part "Resistor"))
    )
    (comp (ref "R24")
      (value "47 kOhms")
      (footprint "YAGEO RES 0402_1005")
      (description "RES 47K OHM 1% 1/16W 0402")
      (fields (field (name "TOLERANCE") "±1%") (field (name "MANUFACTURER") "Yageo"))
      (libsource (lib "Celestial Altium Library - altium_library") (part "Resistor"))
    )
    (comp (ref "R25")
      (value "47 kOhms")
      (footprint "YAGEO RES 0402_1005")
      (description "RES 47K OHM 1% 1/16W 0402")
      (fields (field (name "TOLERANCE") "±1%") (field (name "MANUFACTURER") "Yageo"))
      (libsource (lib "Celestial Altium Library - altium_library") (part "Resistor"))
    )
    (comp (ref "R26")
      (value "0 Ohms")
      (footprint "YAGEO RES 0402_1005")
      (description "RES 0 OHM JUMPER 1/16W 0402")
      (fields (field (name "TOLERANCE") "Jumper") (field (name "MANUFACTURER") "Yageo"))
      (libsource (lib "Celestial Altium Library - altium_library") (part "Resistor"))
    )
    (comp (ref "R27")
      (value "0 Ohms")
      (footprint "YAGEO RES 0402_1005")
      (description "RES 0 OHM JUMPER 1/16W 0402")
      (fields (field (name "TOLERANCE") "Jumper") (field (name "MANUFACTURER") "Yageo"))
      (libsource (lib "Celestial Altium Library - altium_library") (part "Resistor"))
    )
    (comp (ref "R28")
      (value "200 Ohms")
      (footprint "YAGEO RES 0402_1005")
      (description "RES 200 OHM 1% 1/16W 0402")
      (fields (field (name "MANUFACTURER") "Yageo") (field (name "PART NUMBER") "RC0402FR-07200RL"))
      (libsource (lib "Celestial Altium Library - altium_library") (part "Resistor"))
    )
    (comp (ref "R29")
      (value "5.1 kOhms")
      (footprint "YAGEO RES 0402_1005")
      (description "RES 5.1K OHM 1% 1/16W 0402")
      (fields (field (name "TOLERANCE") "±1%") (field (name "MANUFACTURER") "Yageo"))
      (libsource (lib "Celestial Altium Library - altium_library") (part "Resistor"))
    )
    (comp (ref "R30")
      (value "1 MOhms")
      (footprint "YAGEO RES 0402_1005")
      (description "RES 1M OHM 1% 1/16W 0402")
      (fields (field (name "TOLERANCE") "±1%") (field (name "MANUFACTURER") "Yageo"))
      (libsource (lib "Celestial Altium Library - altium_library") (part "Resistor"))
    )
    (comp (ref "R31")
      (value "5.1 kOhms")
      (footprint "YAGEO RES 0402_1005")
      (description "RES 5.1K OHM 1% 1/16W 0402")
      (fields (field (name "TOLERANCE") "±1%") (field (name "MANUFACTURER") "Yageo"))
      (libsource (lib "Celestial Altium Library - altium_library") (part "Resistor"))
    )
    (comp (ref "R32")
      (value "4.7 kOhms")
      (footprint "YAGEO RES 0402_1005")
      (description "RES 4.7K OHM 1% 1/16W 0402")
      (fields (field (name "TOLERANCE") "±1%") (field (name "MANUFACTURER") "Yageo"))
      (libsource (lib "Celestial Altium Library - altium_library") (part "Resistor"))
    )
    (comp (ref "R33")
      (value "4.7 kOhms")
      (footprint "YAGEO RES 0402_1005")
      (description "RES 4.7K OHM 1% 1/16W 0402")
      (fields (field (name "TOLERANCE") "±1%") (field (name "MANUFACTURER") "Yageo"))
      (libsource (lib "Celestial Altium Library - altium_library") (part "Resistor"))
    )
    (comp (ref "R34")
      (value "4.7 kOhms")
      (footprint "YAGEO RES 0402_1005")
      (description "RES 4.7K OHM 1% 1/16W 0402")
      (fields (field (name "TOLERANCE") "±1%") (field (name "MANUFACTURER") "Yageo"))
      (libsource (lib "Celestial Altium Library - altium_library") (part "Resistor"))
    )
    (comp (ref "R35")
      (value "4.7 kOhms")
      (footprint "YAGEO RES 0402_1005")
      (description "RES 4.7K OHM 1% 1/16W 0402")
      (fields (field (name "TOLERANCE") "±1%") (field (name "MANUFACTURER") "Yageo"))
      (libsource (lib "Celestial Altium Library - altium_library") (part "Resistor"))
    )
    (comp (ref "R36")
      (value "22 Ohms")
      (footprint "YAGEO RES 0402_1005")
      (description "RES 22 OHM 1% 1/16W 0402")
      (fields (field (name "TOLERANCE") "±1%") (field (name "MANUFACTURER") "Yageo"))
      (libsource (lib "Celestial Altium Library - altium_library") (part "Resistor"))
    )
    (comp (ref "R37")
      (value "10 kOhms")
      (footprint "YAGEO RES 0402_1005")
      (description "RES 10K OHM 1% 1/16W 0402")
      (fields (field (name "TOLERANCE") "±1%") (field (name "MANUFACTURER") "Yageo"))
      (libsource (lib "Celestial Altium Library - altium_library") (part "Resistor"))
    )
    (comp (ref "R38")
      (value "39.2 kOhms")
      (footprint "YAGEO RES 0402_1005")
      (description "RES 39.2K OHM 1% 1/16W 0402")
      (fields (field (name "TOLERANCE") "±1%") (field (name "MANUFACTURER") "Yageo"))
      (libsource (lib "Celestial Altium Library - altium_library") (part "Resistor"))
    )
    (comp (ref "SW1")
      (value "218-4LPST")
      (footprint "CTS 218-4LPJ")
      (description "SWITCH SLIDE DIP SPST 25MA 24V")
      (fields (field (name "MANUFACTURER") "CTS Electrocomponents"))
      (libsource (lib "Celestial Altium Library - altium_library") (part "DIP SW 4P"))
    )
    (comp (ref "TP1")
      (value "PAD_TEST")
      (footprint "Samacsys:PAD_TEST")
      (description "Test Point")
      (fields (field (name "TOLERANCE") "{Tolerance}") (field (name "MANUFACTURER") "{Manufacturer}"))
      (libsource (lib "SamacSys") (part "PAD_TEST"))
    )
    (comp (ref "TP2")
      (value "PAD_TEST")
      (footprint "Samacsys:PAD_TEST")
      (description "Test Point")
      (fields (field (name "TOLERANCE") "{Tolerance}") (field (name "MANUFACTURER") "{Manufacturer}"))
      (libsource (lib "SamacSys") (part "PAD_TEST"))
    )
    (comp (ref "U1")
      (value "NC7WZ125K8X")
      (footprint "SamacSys:SOP50P310X90-8N")
      (description "Integrated Circuit")
      (libsource (lib "") (part "NC7WZ125K8X_1"))
    )
    (comp (ref "U2")
      (value "SN74LVC1G3157DBVR")
      (footprint "SamacSys:SOT95P280X145-6N")
      (description "Integrated Circuit")
      (fields (field (name "MOUSER PART NUMBER") "595-SN74LVC1G3157DBV"))
      (libsource (lib "SamacSys") (part "SN74LVC1G3157DBVR"))
    )
    (comp (ref "U3")
      (value "SN74LVC1G3157DBVR")
      (footprint "SamacSys:SOT95P280X145-6N")
      (description "Integrated Circuit")
      (fields (field (name "MOUSER PART NUMBER") "595-SN74LVC1G3157DBV"))
      (libsource (lib "") (part "SN74LVC1G3157DBVR_1"))
    )
    (comp (ref "U4")
      (value "NC7WZ125K8X")
      (footprint "SamacSys:SOP50P310X90-8N")
      (description "Integrated Circuit")
      (libsource (lib "SamacSys") (part "NC7WZ125K8X"))
    )
    (comp (ref "U5")
      (value "SN74LVC1G3157DBVR")
      (footprint "SamacSys:SOT95P280X145-6N")
      (description "Integrated Circuit")
      (fields (field (name "MOUSER PART NUMBER") "595-SN74LVC1G3157DBV"))
      (libsource (lib "") (part "SN74LVC1G3157DBVR_1"))
    )
    (comp (ref "U6")
      (value "SN74LVC1G3157DBVR")
      (footprint "SamacSys:SOT95P280X145-6N")
      (description "Integrated Circuit")
      (fields (field (name "MOUSER PART NUMBER") "595-SN74LVC1G3157DBV"))
      (libsource (lib "SamacSys") (part "SN74LVC1G3157DBVR"))
    )
    (comp (ref "U7")
      (value "AX88279")
      (footprint "IC_AX88279")
      (libsource (lib "LotusSound") (part "IC_AX88279"))
    )
    (comp (ref "U8")
      (value "ESD7016MUTAG")
      (footprint "ONSC-UDFN-8-517CB_V")
      (description "Low Capacitance ESD Protection USB 3.0, 8-Pin UDFN, Pb-Free, Tape and Reel")
      (fields (field (name "MANUFACTURER") "On Semiconductor"))
      (libsource (lib "Altium Content Vault") (part "ONSC-ESD7016-UDFN-8-517CB"))
    )
    (comp (ref "U9")
      (value "ST1S06PU33R")
      (footprint "DFN6D_L")
      (fields (field (name "MANUFACTURER") "STMicroelectronics"))
      (libsource (lib "Altium Content Vault") (part "PM-DCDC-ST1S06-IL7"))
    )
    (comp (ref "U10")
      (value "SST25VF016B-50-4I-QAF-T")
      (footprint "FP-C04-452-MFG")
      (libsource (lib "Altium Content Vault") (part "d7313dde12fd16fde488169701056cc"))
    )
    (comp (ref "U11")
      (value "ST1S06PUR")
      (footprint "DFN6D_M")
      (libsource (lib "Altium Content Vault") (part "PM-DCDC-ST1S06-IL7"))
    )
    (comp (ref "Y1")
      (value "25 MHz")
      (footprint "NDK NX3225GA")
      (description "CRYSTAL 25.0000MHZ 8PF SMD")
      (fields
        (field (name "MANUFACTURER") "NDK America, Inc.")
        (field (name "PART NUMBER") "NX3225GA-25.000M-STD-CRG-2")
      )
      (libsource (lib "Celestial Altium Library - altium_library") (part "NDK Crystal NX3225GA"))
    )
  )
  (nets
    (net (code "1") (name "/1PPS_IN") (class "Default")
      (node (ref "R11") (pin "1") (pinfunction "1_1") (pintype "passive"))
      (node (ref "U4") (pin "2") (pinfunction "A1_2") (pintype "passive"))
      (node (ref "U4") (pin "5") (pinfunction "A2_5") (pintype "passive"))
      (node (ref "U6") (pin "4") (pinfunction "A_4") (pintype "passive"))
    )
    (net (code "2") (name "/1PPS_IN_BUFF") (class "Default")
      (node (ref "R11") (pin "2") (pinfunction "2_2") (pintype "passive"))
      (node (ref "U2") (pin "3") (pinfunction "B1_3") (pintype "passive"))
      (node (ref "U4") (pin "3") (pinfunction "Y2_3") (pintype "passive"))
    )
    (net (code "3") (name "/1PPS_IN_LED") (class "Default")
      (node (ref "D2") (pin "1") (pinfunction "C_1") (pintype "passive"))
      (node (ref "U4") (pin "6") (pinfunction "Y1_6") (pintype "passive"))
    )
    (net (code "4") (name "/1PPS_OUT") (class "Default")
      (node (ref "R7") (pin "2") (pinfunction "2_2") (pintype "passive"))
      (node (ref "U1") (pin "2") (pinfunction "A1_2") (pintype "passive"))
      (node (ref "U1") (pin "5") (pinfunction "A2_5") (pintype "passive"))
      (node (ref "U2") (pin "1") (pinfunction "B2_1") (pintype "passive"))
    )
    (net (code "5") (name "/1PPS_OUT_BUFF") (class "Default")
      (node (ref "R7") (pin "1") (pinfunction "1_1") (pintype "passive"))
      (node (ref "U1") (pin "3") (pinfunction "Y2_3") (pintype "passive"))
      (node (ref "U3") (pin "1") (pinfunction "B2_1") (pintype "passive"))
    )
    (net (code "6") (name "/1PPS_OUT_LED") (class "Default")
      (node (ref "D1") (pin "1") (pinfunction "C_1") (pintype "passive"))
      (node (ref "U1") (pin "6") (pinfunction "Y1_6") (pintype "passive"))
    )
    (net (code "7") (name "/1PPS_SMA_IO") (class "Default")
      (node (ref "J1") (pin "1") (pinfunction "1_1") (pintype "passive"))
      (node (ref "U3") (pin "4") (pinfunction "A_4") (pintype "passive"))
      (node (ref "U5") (pin "1") (pinfunction "B2_1") (pintype "passive"))
    )
    (net (code "8") (name "/279_1PPS_IO") (class "Default")
      (node (ref "U2") (pin "4") (pinfunction "A_4") (pintype "passive"))
      (node (ref "U7") (pin "46") (pinfunction "GPIO14(1588_PSS)_46") (pintype "passive"))
    )
    (net (code "9") (name "/279_TOD_IN") (class "Default")
      (node (ref "IC1") (pin "2") (pinfunction "TXD_2") (pintype "passive"))
      (node (ref "IC2") (pin "20") (pinfunction "TXD_/_SPI_MISO_20") (pintype "passive"))
      (node (ref "J3") (pin "3") (pinfunction "3_3") (pintype "passive"))
      (node (ref "R23") (pin "1") (pinfunction "1_1") (pintype "passive"))
    )
    (net (code "10") (name "/279_TOD_IN_R") (class "Default")
      (node (ref "R23") (pin "2") (pinfunction "2_2") (pintype "passive"))
      (node (ref "U7") (pin "20") (pinfunction "GPIO6_20") (pintype "passive"))
    )
    (net (code "11") (name "/279_TOD_OUT") (class "Default")
      (node (ref "IC1") (pin "3") (pinfunction "RXD_3") (pintype "passive"))
      (node (ref "IC2") (pin "21") (pinfunction "RXD_/_SPI_MOSI_21") (pintype "passive"))
      (node (ref "J3") (pin "4") (pinfunction "4_4") (pintype "passive"))
      (node (ref "R26") (pin "1") (pinfunction "1_1") (pintype "passive"))
    )
    (net (code "12") (name "/279_TOD_OUT_R") (class "Default")
      (node (ref "R26") (pin "2") (pinfunction "2_2") (pintype "passive"))
      (node (ref "U7") (pin "21") (pinfunction "GPIO7_21") (pintype "passive"))
    )
    (net (code "13") (name "/ANT") (class "Default")
      (node (ref "FB1") (pin "2") (pinfunction "2_2") (pintype "passive"))
      (node (ref "IC1") (pin "11") (pinfunction "RF_IN_11") (pintype "passive"))
      (node (ref "IC2") (pin "11") (pinfunction "RF_IN_11") (pintype "passive"))
      (node (ref "J2") (pin "1") (pinfunction "1_1") (pintype "passive"))
    )
    (net (code "14") (name "/AVDD10") (class "Default")
      (node (ref "C16") (pin "2") (pinfunction "2_2") (pintype "passive"))
      (node (ref "C17") (pin "2") (pinfunction "2_2") (pintype "passive"))
      (node (ref "FB2") (pin "2") (pinfunction "2_2") (pintype "passive"))
      (node (ref "U7") (pin "43") (pinfunction "AVDD10_SSUSB_43") (pintype "passive"))
    )
    (net (code "15") (name "/AVDD_1.85") (class "Default")
      (node (ref "C39") (pin "2") (pinfunction "2_2") (pintype "passive"))
      (node (ref "C40") (pin "2") (pinfunction "2_2") (pintype "passive"))
      (node (ref "FB3") (pin "2") (pinfunction "2_2") (pintype "passive"))
      (node (ref "FB5") (pin "2") (pinfunction "2_2") (pintype "passive"))
      (node (ref "U7") (pin "40") (pinfunction "AVDD18_SSUSB_40") (pintype "passive"))
      (node (ref "U7") (pin "8") (pinfunction "AVDD18_COM_8") (pintype "passive"))
    )
    (net (code "16") (name "/AVDD_33") (class "Default")
      (node (ref "C29") (pin "2") (pinfunction "2_2") (pintype "passive"))
      (node (ref "C30") (pin "2") (pinfunction "2_2") (pintype "passive"))
      (node (ref "C31") (pin "2") (pinfunction "2_2") (pintype "passive"))
      (node (ref "C32") (pin "2") (pinfunction "2_2") (pintype "passive"))
      (node (ref "C33") (pin "2") (pinfunction "2_2") (pintype "passive"))
      (node (ref "FB4") (pin "2") (pinfunction "2_2") (pintype "passive"))
      (node (ref "U7") (pin "12") (pinfunction "AVDD33_LD_12") (pintype "passive"))
      (node (ref "U7") (pin "37") (pinfunction "GPIO13/AVD33_USB_37") (pintype "passive"))
      (node (ref "U7") (pin "5") (pinfunction "AVD33_LD_5") (pintype "passive"))
    )
    (net (code "17") (name "/DVDD_1.85") (class "Default")
      (node (ref "C22") (pin "2") (pinfunction "2_2") (pintype "passive"))
      (node (ref "C36") (pin "2") (pinfunction "2_2") (pintype "passive"))
      (node (ref "C37") (pin "2") (pinfunction "2_2") (pintype "passive"))
      (node (ref "C38") (pin "2") (pinfunction "2_2") (pintype "passive"))
      (node (ref "FB5") (pin "1") (pinfunction "1_1") (pintype "passive"))
      (node (ref "U7") (pin "26") (pinfunction "DVDD18_26") (pintype "passive"))
      (node (ref "U7") (pin "35") (pinfunction "DVDD18_35") (pintype "passive"))
      (node (ref "U7") (pin "53") (pinfunction "DVDD18_53") (pintype "passive"))
      (node (ref "U7") (pin "56") (pinfunction "LDO18_56") (pintype "passive"))
    )
    (net (code "18") (name "/D_N") (class "Default")
      (node (ref "J5") (pin "A7") (pinfunction "Dn1_A7") (pintype "passive"))
      (node (ref "J5") (pin "B7") (pinfunction "Dn2_B7") (pintype "passive"))
      (node (ref "U7") (pin "38") (pinfunction "GPIO12_USB_DN_38") (pintype "passive"))
      (node (ref "U8") (pin "5") (pinfunction "I/O_5") (pintype "passive"))
    )
    (net (code "19") (name "/D_P") (class "Default")
      (node (ref "J5") (pin "A6") (pinfunction "Dp1_A6") (pintype "passive"))
      (node (ref "J5") (pin "B6") (pinfunction "Dp2_B6") (pintype "passive"))
      (node (ref "U7") (pin "39") (pinfunction "GPIO12_USB_DP_39") (pintype "passive"))
      (node (ref "U8") (pin "4") (pinfunction "I/O_4") (pintype "passive"))
    )
    (net (code "20") (name "/GPS_PPS_OUT") (class "Default")
      (node (ref "IC1") (pin "4") (pinfunction "TIMEPULSE_4") (pintype "passive"))
      (node (ref "IC2") (pin "3") (pinfunction "TIMEPULSE_3") (pintype "passive"))
      (node (ref "J3") (pin "5") (pinfunction "5_5") (pintype "passive"))
      (node (ref "U5") (pin "4") (pinfunction "A_4") (pintype "passive"))
    )
    (net (code "21") (name "/LED0") (class "Default")
      (node (ref "J4") (pin "P12") (pinfunction "K_GREEN_P12") (pintype "passive"))
      (node (ref "R18") (pin "2") (pinfunction "2_2") (pintype "passive"))
      (node (ref "U7") (pin "27") (pinfunction "GPIO5(LED0)_27") (pintype "passive"))
    )
    (net (code "22") (name "/LED1") (class "Default")
      (node (ref "J4") (pin "P14") (pinfunction "K_YELLOW_P14") (pintype "passive"))
      (node (ref "R19") (pin "2") (pinfunction "2_2") (pintype "passive"))
      (node (ref "U7") (pin "28") (pinfunction "GPIO4(LED1)_28") (pintype "passive"))
    )
    (net (code "23") (name "/MDI0_N") (class "Default")
      (node (ref "J4") (pin "P2") (pinfunction "TD1-_P2") (pintype "passive"))
      (node (ref "U7") (pin "4") (pinfunction "TXVN_A_4") (pintype "passive"))
    )
    (net (code "24") (name "/MDI0_P") (class "Default")
      (node (ref "J4") (pin "P1") (pinfunction "TD1+_P1") (pintype "passive"))
      (node (ref "U7") (pin "3") (pinfunction "TXVP_A_3") (pintype "passive"))
    )
    (net (code "25") (name "/MDI1_N") (class "Default")
      (node (ref "J4") (pin "P4") (pinfunction "TD2-_P4") (pintype "passive"))
      (node (ref "U7") (pin "7") (pinfunction "TXVP_B_7") (pintype "passive"))
    )
    (net (code "26") (name "/MDI1_P") (class "Default")
      (node (ref "J4") (pin "P3") (pinfunction "TD2+_P3") (pintype "passive"))
      (node (ref "U7") (pin "6") (pinfunction "TXVP_B_6") (pintype "passive"))
    )
    (net (code "27") (name "/MDI2_N") (class "Default")
      (node (ref "J4") (pin "P6") (pinfunction "TD3-_P6") (pintype "passive"))
      (node (ref "U7") (pin "11") (pinfunction "TXVN_C_11") (pintype "passive"))
    )
    (net (code "28") (name "/MDI2_P") (class "Default")
      (node (ref "J4") (pin "P5") (pinfunction "TD3+_P5") (pintype "passive"))
      (node (ref "U7") (pin "10") (pinfunction "TXVP_C_10") (pintype "passive"))
    )
    (net (code "29") (name "/MDI3_N") (class "Default")
      (node (ref "J4") (pin "P8") (pinfunction "TD4-_P8") (pintype "passive"))
      (node (ref "U7") (pin "14") (pinfunction "TXVN_D_14") (pintype "passive"))
    )
    (net (code "30") (name "/MDI3_P") (class "Default")
      (node (ref "J4") (pin "P7") (pinfunction "TD4+_P7") (pintype "passive"))
      (node (ref "U7") (pin "13") (pinfunction "TXVP_D_13") (pintype "passive"))
    )
    (net (code "31") (name "/MUX1_CTRL") (class "Default")
      (node (ref "R3") (pin "1") (pinfunction "1_1") (pintype "passive"))
      (node (ref "SW1") (pin "8") (pinfunction "8_8") (pintype "passive"))
      (node (ref "U3") (pin "6") (pinfunction "S_6") (pintype "passive"))
    )
    (net (code "32") (name "/MUX2_CTRL") (class "Default")
      (node (ref "R4") (pin "1") (pinfunction "1_1") (pintype "passive"))
      (node (ref "SW1") (pin "7") (pinfunction "7_7") (pintype "passive"))
      (node (ref "U2") (pin "6") (pinfunction "S_6") (pintype "passive"))
    )
    (net (code "33") (name "/MUX3_CTRL") (class "Default")
      (node (ref "R5") (pin "1") (pinfunction "1_1") (pintype "passive"))
      (node (ref "SW1") (pin "6") (pinfunction "6_6") (pintype "passive"))
      (node (ref "U6") (pin "6") (pinfunction "S_6") (pintype "passive"))
    )
    (net (code "34") (name "/MUX4_CTRL") (class "Default")
      (node (ref "R6") (pin "1") (pinfunction "1_1") (pintype "passive"))
      (node (ref "SW1") (pin "5") (pinfunction "5_5") (pintype "passive"))
      (node (ref "U5") (pin "6") (pinfunction "S_6") (pintype "passive"))
    )
    (net (code "35") (name "/RESET_N") (class "Default")
      (node (ref "R16") (pin "1") (pinfunction "1_1") (pintype "passive"))
      (node (ref "U7") (pin "23") (pinfunction "HW_RSTN_23") (pintype "passive"))
    )
    (net (code "36") (name "/SB") (class "Default")
      (node (ref "IC1") (pin "18") (pinfunction "SAFEBOOT_N_18") (pintype "passive"))
      (node (ref "IC2") (pin "1") (pinfunction "SAFEBOOT_N_1") (pintype "passive"))
      (node (ref "R15") (pin "1") (pinfunction "1_1") (pintype "passive"))
    )
    (net (code "37") (name "/SCL") (class "Default")
      (node (ref "IC1") (pin "17") (pinfunction "SCL_17") (pintype "passive"))
      (node (ref "IC2") (pin "19") (pinfunction "SCL_/_SPI_SLK__19") (pintype "passive"))
      (node (ref "TP2") (pin "1") (pinfunction "1_1") (pintype "passive"))
    )
    (net (code "38") (name "/SDA") (class "Default")
      (node (ref "IC1") (pin "16") (pinfunction "SDA_16") (pintype "passive"))
      (node (ref "IC2") (pin "18") (pinfunction "SDA_/_SPI_CS_N_18") (pintype "passive"))
      (node (ref "TP1") (pin "1") (pinfunction "1_1") (pintype "passive"))
    )
    (net (code "39") (name "/SPI_CLK") (class "Default")
      (node (ref "R33") (pin "2") (pinfunction "2_2") (pintype "passive"))
      (node (ref "U10") (pin "6") (pinfunction "SCK_6") (pintype "input"))
      (node (ref "U7") (pin "51") (pinfunction "SPI_CLK_51") (pintype "passive"))
    )
    (net (code "40") (name "/SPI_CS") (class "Default")
      (node (ref "U10") (pin "1") (pinfunction "~{CE}_1") (pintype "input"))
      (node (ref "U7") (pin "50") (pinfunction "SPI_CS0_50") (pintype "passive"))
    )
    (net (code "41") (name "/SPI_DIO") (class "Default")
      (node (ref "R32") (pin "2") (pinfunction "2_2") (pintype "passive"))
      (node (ref "R36") (pin "2") (pinfunction "2_2") (pintype "passive"))
      (node (ref "U10") (pin "5") (pinfunction "SI_5") (pintype "input"))
      (node (ref "U7") (pin "52") (pinfunction "SPI_DIO_52") (pintype "passive"))
    )
    (net (code "42") (name "/SSRX_N") (class "Default")
      (node (ref "J5") (pin "A10") (pinfunction "SSRXn2_A10") (pintype "passive"))
      (node (ref "J5") (pin "B10") (pinfunction "SSRXn1_B10") (pintype "passive"))
      (node (ref "U7") (pin "44") (pinfunction "SSUSBRXN_44") (pintype "passive"))
      (node (ref "U8") (pin "7") (pinfunction "I/O_7") (pintype "passive"))
    )
    (net (code "43") (name "/SSRX_P") (class "Default")
      (node (ref "J5") (pin "A11") (pinfunction "SSRXp2_A11") (pintype "passive"))
      (node (ref "J5") (pin "B11") (pinfunction "SSRXp1_B11") (pintype "passive"))
      (node (ref "U7") (pin "45") (pinfunction "SSUSBRXP_45") (pintype "passive"))
      (node (ref "U8") (pin "8") (pinfunction "I/O_8") (pintype "passive"))
    )
    (net (code "44") (name "/SSTX_N") (class "Default")
      (node (ref "C11") (pin "2") (pinfunction "2_2") (pintype "passive"))
      (node (ref "U7") (pin "41") (pinfunction "SSUSB_TXN_41") (pintype "passive"))
    )
    (net (code "45") (name "/SSTX_P") (class "Default")
      (node (ref "C10") (pin "2") (pinfunction "2_2") (pintype "passive"))
      (node (ref "U7") (pin "42") (pinfunction "SSUSB_TXP_42") (pintype "passive"))
    )
    (net (code "46") (name "/USB3.0_SSTX_N") (class "Default")
      (node (ref "C11") (pin "1") (pinfunction "1_1") (pintype "passive"))
      (node (ref "J5") (pin "A3") (pinfunction "SSTXn1_A3") (pintype "passive"))
      (node (ref "J5") (pin "B3") (pinfunction "SSTXn2_B3") (pintype "passive"))
      (node (ref "U8") (pin "1") (pinfunction "I/O_1") (pintype "passive"))
    )
    (net (code "47") (name "/USB3.0_SSTX_P") (class "Default")
      (node (ref "C10") (pin "1") (pinfunction "1_1") (pintype "passive"))
      (node (ref "J5") (pin "A2") (pinfunction "SSTXp1_A2") (pintype "passive"))
      (node (ref "J5") (pin "B2") (pinfunction "SSTXp2_B2") (pintype "passive"))
      (node (ref "U8") (pin "2") (pinfunction "I/O_2") (pintype "passive"))
    )
    (net (code "48") (name "/VBUS") (class "Default")
      (node (ref "R14") (pin "1") (pinfunction "1_1") (pintype "passive"))
      (node (ref "R17") (pin "2") (pinfunction "2_2") (pintype "passive"))
      (node (ref "U7") (pin "34") (pinfunction "GPIO9(VBUS)_34") (pintype "passive"))
    )
    (net (code "49") (name "/VCC_RF") (class "Default")
      (node (ref "IC1") (pin "14") (pinfunction "VCC_RF_14") (pintype "passive"))
      (node (ref "IC2") (pin "9") (pinfunction "VCC_RF_9") (pintype "passive"))
      (node (ref "R20") (pin "1") (pinfunction "1_1") (pintype "passive"))
    )
    (net (code "50") (name "/VCORE_LDO") (class "Default")
      (node (ref "C21") (pin "2") (pinfunction "2_2") (pintype "passive"))
      (node (ref "FB2") (pin "1") (pinfunction "1_1") (pintype "passive"))
      (node (ref "U7") (pin "55") (pinfunction "VCORE_LDO_55") (pintype "passive"))
    )
    (net (code "51") (name "/XTL20N") (class "Default")
      (node (ref "R28") (pin "2") (pinfunction "2_2") (pintype "passive"))
      (node (ref "U7") (pin "16") (pinfunction "XTAL_XO_16") (pintype "passive"))
    )
    (net (code "52") (name "/XTL20P") (class "Default")
      (node (ref "R27") (pin "2") (pinfunction "2_2") (pintype "passive"))
      (node (ref "U7") (pin "17") (pinfunction "XTAL_IN_17") (pintype "passive"))
    )
    (net (code "53") (name "CHASSIS_GND") (class "Default")
      (node (ref "C9") (pin "1") (pinfunction "1_1") (pintype "passive"))
      (node (ref "J4") (pin "MH1") (pinfunction "MH1_MH1") (pintype "passive"))
      (node (ref "J4") (pin "MH2") (pinfunction "MH2_MH2") (pintype "passive"))
      (node (ref "R13") (pin "1") (pinfunction "1_1") (pintype "passive"))
    )
    (net (code "54") (name "DVDD_33") (class "Default")
      (node (ref "C18") (pin "2") (pinfunction "2_2") (pintype "passive"))
      (node (ref "C19") (pin "2") (pinfunction "2_2") (pintype "passive"))
      (node (ref "C25") (pin "2") (pinfunction "2_2") (pintype "passive"))
      (node (ref "C26") (pin "2") (pinfunction "2_2") (pintype "passive"))
      (node (ref "C27") (pin "2") (pinfunction "2_2") (pintype "passive"))
      (node (ref "C28") (pin "2") (pinfunction "2_2") (pintype "passive"))
      (node (ref "C7") (pin "2") (pinfunction "2_2") (pintype "passive"))
      (node (ref "C8") (pin "2") (pinfunction "2_2") (pintype "passive"))
      (node (ref "FB4") (pin "1") (pinfunction "1_1") (pintype "passive"))
      (node (ref "IC1") (pin "7") (pinfunction "V_IO_7") (pintype "passive"))
      (node (ref "IC1") (pin "8") (pinfunction "VCC_8") (pintype "passive"))
      (node (ref "IC2") (pin "2") (pinfunction "D_SEL_2") (pintype "passive"))
      (node (ref "IC2") (pin "23") (pinfunction "VCC_23") (pintype "passive"))
      (node (ref "IC2") (pin "7") (pinfunction "V_USB_7") (pintype "passive"))
      (node (ref "L1") (pin "2") (pinfunction "2_2") (pintype "passive"))
      (node (ref "R10") (pin "2") (pinfunction "2_2") (pintype "passive"))
      (node (ref "R12") (pin "2") (pinfunction "2_2") (pintype "passive"))
      (node (ref "R16") (pin "2") (pinfunction "2_2") (pintype "passive"))
      (node (ref "R18") (pin "1") (pinfunction "1_1") (pintype "passive"))
      (node (ref "R19") (pin "1") (pinfunction "1_1") (pintype "passive"))
      (node (ref "R22") (pin "2") (pinfunction "2_2") (pintype "passive"))
      (node (ref "R24") (pin "2") (pinfunction "2_2") (pintype "passive"))
      (node (ref "R25") (pin "2") (pinfunction "2_2") (pintype "passive"))
      (node (ref "R32") (pin "1") (pinfunction "1_1") (pintype "passive"))
      (node (ref "R33") (pin "1") (pinfunction "1_1") (pintype "passive"))
      (node (ref "R34") (pin "1") (pinfunction "1_1") (pintype "passive"))
      (node (ref "R35") (pin "1") (pinfunction "1_1") (pintype "passive"))
      (node (ref "U10") (pin "8") (pinfunction "VDD_8") (pintype "power_in"))
      (node (ref "U7") (pin "25") (pinfunction "DVDD33_25") (pintype "passive"))
      (node (ref "U7") (pin "36") (pinfunction "DVDD33_36") (pintype "passive"))
      (node (ref "U7") (pin "54") (pinfunction "AVDD33_LDO_54") (pintype "passive"))
      (node (ref "U7") (pin "59") (pinfunction "AVD33_BUCK_59") (pintype "passive"))
      (node (ref "U9") (pin "1") (pinfunction "VO/VFB_1") (pintype "bidirectional"))
    )
    (net (code "55") (name "GND") (class "Default")
      (node (ref "C1") (pin "1") (pinfunction "1_1") (pintype "passive"))
      (node (ref "C12") (pin "1") (pinfunction "1_1") (pintype "passive"))
      (node (ref "C13") (pin "1") (pinfunction "1_1") (pintype "passive"))
      (node (ref "C14") (pin "1") (pinfunction "1_1") (pintype "passive"))
      (node (ref "C15") (pin "1") (pinfunction "1_1") (pintype "passive"))
      (node (ref "C16") (pin "1") (pinfunction "1_1") (pintype "passive"))
      (node (ref "C17") (pin "1") (pinfunction "1_1") (pintype "passive"))
      (node (ref "C18") (pin "1") (pinfunction "1_1") (pintype "passive"))
      (node (ref "C19") (pin "1") (pinfunction "1_1") (pintype "passive"))
      (node (ref "C2") (pin "1") (pinfunction "1_1") (pintype "passive"))
      (node (ref "C20") (pin "1") (pinfunction "1_1") (pintype "passive"))
      (node (ref "C21") (pin "1") (pinfunction "1_1") (pintype "passive"))
      (node (ref "C22") (pin "1") (pinfunction "1_1") (pintype "passive"))
      (node (ref "C23") (pin "1") (pinfunction "1_1") (pintype "passive"))
      (node (ref "C24") (pin "1") (pinfunction "1_1") (pintype "passive"))
      (node (ref "C25") (pin "1") (pinfunction "1_1") (pintype "passive"))
      (node (ref "C26") (pin "1") (pinfunction "1_1") (pintype "passive"))
      (node (ref "C27") (pin "1") (pinfunction "1_1") (pintype "passive"))
      (node (ref "C28") (pin "1") (pinfunction "1_1") (pintype "passive"))
      (node (ref "C29") (pin "1") (pinfunction "1_1") (pintype "passive"))
      (node (ref "C3") (pin "1") (pinfunction "1_1") (pintype "passive"))
      (node (ref "C30") (pin "1") (pinfunction "1_1") (pintype "passive"))
      (node (ref "C31") (pin "1") (pinfunction "1_1") (pintype "passive"))
      (node (ref "C32") (pin "1") (pinfunction "1_1") (pintype "passive"))
      (node (ref "C33") (pin "1") (pinfunction "1_1") (pintype "passive"))
      (node (ref "C34") (pin "1") (pinfunction "1_1") (pintype "passive"))
      (node (ref "C35") (pin "1") (pinfunction "1_1") (pintype "passive"))
      (node (ref "C36") (pin "1") (pinfunction "1_1") (pintype "passive"))
      (node (ref "C37") (pin "1") (pinfunction "1_1") (pintype "passive"))
      (node (ref "C38") (pin "1") (pinfunction "1_1") (pintype "passive"))
      (node (ref "C39") (pin "1") (pinfunction "1_1") (pintype "passive"))
      (node (ref "C4") (pin "1") (pinfunction "1_1") (pintype "passive"))
      (node (ref "C40") (pin "1") (pinfunction "1_1") (pintype "passive"))
      (node (ref "C41") (pin "1") (pinfunction "1_1") (pintype "passive"))
      (node (ref "C42") (pin "1") (pinfunction "1_1") (pintype "passive"))
      (node (ref "C43") (pin "1") (pinfunction "1_1") (pintype "passive"))
      (node (ref "C44") (pin "1") (pinfunction "1_1") (pintype "passive"))
      (node (ref "C5") (pin "1") (pinfunction "1_1") (pintype "passive"))
      (node (ref "C6") (pin "1") (pinfunction "1_1") (pintype "passive"))
      (node (ref "C7") (pin "1") (pinfunction "1_1") (pintype "passive"))
      (node (ref "C8") (pin "1") (pinfunction "1_1") (pintype "passive"))
      (node (ref "C9") (pin "2") (pinfunction "2_2") (pintype "passive"))
      (node (ref "IC1") (pin "1") (pinfunction "GND_1_1") (pintype "passive"))
      (node (ref "IC1") (pin "10") (pinfunction "GND_2_10") (pintype "passive"))
      (node (ref "IC1") (pin "12") (pinfunction "GND_3_12") (pintype "passive"))
      (node (ref "IC2") (pin "10") (pinfunction "GND_1_10") (pintype "passive"))
      (node (ref "IC2") (pin "12") (pinfunction "GND_2_12") (pintype "passive"))
      (node (ref "IC2") (pin "13") (pinfunction "GND_3_13") (pintype "passive"))
      (node (ref "IC2") (pin "24") (pinfunction "GND_4_24") (pintype "passive"))
      (node (ref "J1") (pin "2") (pinfunction "2_2") (pintype "passive"))
      (node (ref "J1") (pin "3") (pinfunction "3_3") (pintype "passive"))
      (node (ref "J1") (pin "4") (pinfunction "4_4") (pintype "passive"))
      (node (ref "J1") (pin "5") (pinfunction "5_5") (pintype "passive"))
      (node (ref "J2") (pin "2") (pinfunction "2_2") (pintype "passive"))
      (node (ref "J2") (pin "3") (pinfunction "3_3") (pintype "passive"))
      (node (ref "J2") (pin "4") (pinfunction "4_4") (pintype "passive"))
      (node (ref "J2") (pin "5") (pinfunction "5_5") (pintype "passive"))
      (node (ref "J3") (pin "1") (pinfunction "1_1") (pintype "passive"))
      (node (ref "J4") (pin "P10") (pinfunction "GND_P10") (pintype "passive"))
      (node (ref "J5") (pin "A1") (pinfunction "GND_A1") (pintype "passive"))
      (node (ref "J5") (pin "A12") (pinfunction "GND_A12") (pintype "passive"))
      (node (ref "J5") (pin "B1") (pinfunction "GND_B1") (pintype "passive"))
      (node (ref "J5") (pin "B12") (pinfunction "GND_B12") (pintype "passive"))
      (node (ref "R1") (pin "2") (pinfunction "2_2") (pintype "passive"))
      (node (ref "R13") (pin "2") (pinfunction "2_2") (pintype "passive"))
      (node (ref "R15") (pin "2") (pinfunction "2_2") (pintype "passive"))
      (node (ref "R17") (pin "1") (pinfunction "1_1") (pintype "passive"))
      (node (ref "R21") (pin "1") (pinfunction "1_1") (pintype "passive"))
      (node (ref "R29") (pin "2") (pinfunction "2_2") (pintype "passive"))
      (node (ref "R30") (pin "1") (pinfunction "1_1") (pintype "passive"))
      (node (ref "R31") (pin "2") (pinfunction "2_2") (pintype "passive"))
      (node (ref "R38") (pin "2") (pinfunction "2_2") (pintype "passive"))
      (node (ref "R8") (pin "1") (pinfunction "1_1") (pintype "passive"))
      (node (ref "SW1") (pin "1") (pinfunction "GND_1") (pintype "passive"))
      (node (ref "SW1") (pin "2") (pinfunction "GND_2") (pintype "passive"))
      (node (ref "SW1") (pin "3") (pinfunction "GND_3") (pintype "passive"))
      (node (ref "SW1") (pin "4") (pinfunction "GND_4") (pintype "passive"))
      (node (ref "U1") (pin "4") (pinfunction "GND_4") (pintype "passive"))
      (node (ref "U10") (pin "4") (pinfunction "VSS_4") (pintype "power_in"))
      (node (ref "U10") (pin "9") (pinfunction "VSS_9") (pintype "power_in"))
      (node (ref "U11") (pin "2") (pinfunction "GND_2") (pintype "power_in"))
      (node (ref "U11") (pin "7") (pinfunction "Thermal_Pad_7") (pintype "power_in"))
      (node (ref "U2") (pin "2") (pinfunction "GND_2") (pintype "passive"))
      (node (ref "U3") (pin "2") (pinfunction "GND_2") (pintype "passive"))
      (node (ref "U4") (pin "4") (pinfunction "GND_4") (pintype "passive"))
      (node (ref "U5") (pin "2") (pinfunction "GND_2") (pintype "passive"))
      (node (ref "U6") (pin "2") (pinfunction "GND_2") (pintype "passive"))
      (node (ref "U7") (pin "1") (pinfunction "AVSS33_BUCK_1") (pintype "passive"))
      (node (ref "U7") (pin "2") (pinfunction "AVSS33_BUCK_2") (pintype "passive"))
      (node (ref "U7") (pin "61") (pinfunction "E_PAD_61") (pintype "passive"))
      (node (ref "U8") (pin "6") (pinfunction "GND_6") (pintype "power_in"))
      (node (ref "U9") (pin "2") (pinfunction "GND_2") (pintype "power_in"))
      (node (ref "U9") (pin "7") (pinfunction "Thermal_Pad_7") (pintype "power_in"))
      (node (ref "Y1") (pin "2") (pinfunction "GND_2") (pintype "passive"))
      (node (ref "Y1") (pin "4") (pinfunction "GND_4") (pintype "passive"))
    )
    (net (code "56") (name "Net-(C12-Pad2)") (class "Default")
      (node (ref "C12") (pin "2") (pinfunction "2_2") (pintype "passive"))
      (node (ref "FB1") (pin "1") (pinfunction "1_1") (pintype "passive"))
      (node (ref "R20") (pin "2") (pinfunction "2_2") (pintype "passive"))
    )
    (net (code "57") (name "Net-(C13-Pad2)") (class "Default")
      (node (ref "C13") (pin "2") (pinfunction "2_2") (pintype "passive"))
      (node (ref "R27") (pin "1") (pinfunction "1_1") (pintype "passive"))
      (node (ref "Y1") (pin "1") (pinfunction "1_1") (pintype "passive"))
    )
    (net (code "58") (name "Net-(C14-Pad2)") (class "Default")
      (node (ref "C14") (pin "2") (pinfunction "2_2") (pintype "passive"))
      (node (ref "R28") (pin "1") (pinfunction "1_1") (pintype "passive"))
      (node (ref "Y1") (pin "3") (pinfunction "3_3") (pintype "passive"))
    )
    (net (code "59") (name "Net-(D1-A)") (class "Default")
      (node (ref "D1") (pin "2") (pinfunction "A_2") (pintype "passive"))
      (node (ref "R2") (pin "1") (pinfunction "1_1") (pintype "passive"))
    )
    (net (code "60") (name "Net-(D2-A)") (class "Default")
      (node (ref "D2") (pin "2") (pinfunction "A_2") (pintype "passive"))
      (node (ref "R9") (pin "1") (pinfunction "1_1") (pintype "passive"))
    )
    (net (code "61") (name "Net-(J4-A_GREEN)") (class "Default")
      (node (ref "J4") (pin "P11") (pinfunction "A_GREEN_P11") (pintype "passive"))
      (node (ref "R10") (pin "1") (pinfunction "1_1") (pintype "passive"))
    )
    (net (code "62") (name "Net-(J4-A_YELLOW)") (class "Default")
      (node (ref "J4") (pin "P13") (pinfunction "A_YELLOW_P13") (pintype "passive"))
      (node (ref "R12") (pin "1") (pinfunction "1_1") (pintype "passive"))
    )
    (net (code "63") (name "Net-(J5-CC1)") (class "Default")
      (node (ref "J5") (pin "A5") (pinfunction "CC1_A5") (pintype "passive"))
      (node (ref "R29") (pin "1") (pinfunction "1_1") (pintype "passive"))
    )
    (net (code "64") (name "Net-(J5-CC2)") (class "Default")
      (node (ref "J5") (pin "B5") (pinfunction "CC2_B5") (pintype "passive"))
      (node (ref "R31") (pin "1") (pinfunction "1_1") (pintype "passive"))
    )
    (net (code "65") (name "Net-(J5-Shield)") (class "Default")
      (node (ref "C15") (pin "2") (pinfunction "2_2") (pintype "passive"))
      (node (ref "J5") (pin "S") (pinfunction "Shield_S") (pintype "passive"))
      (node (ref "R30") (pin "2") (pinfunction "2_2") (pintype "passive"))
    )
    (net (code "66") (name "Net-(U1-~{OE1})") (class "Default")
      (node (ref "R1") (pin "1") (pinfunction "1_1") (pintype "passive"))
      (node (ref "U1") (pin "1") (pinfunction "~{OE1}_1") (pintype "passive"))
      (node (ref "U1") (pin "7") (pinfunction "~{OE2}_7") (pintype "passive"))
    )
    (net (code "67") (name "Net-(U3-B1)") (class "Default")
      (node (ref "U3") (pin "3") (pinfunction "B1_3") (pintype "passive"))
      (node (ref "U6") (pin "1") (pinfunction "B2_1") (pintype "passive"))
    )
    (net (code "68") (name "Net-(U4-~{OE1})") (class "Default")
      (node (ref "R8") (pin "2") (pinfunction "2_2") (pintype "passive"))
      (node (ref "U4") (pin "1") (pinfunction "~{OE1}_1") (pintype "passive"))
      (node (ref "U4") (pin "7") (pinfunction "~{OE2}_7") (pintype "passive"))
    )
    (net (code "69") (name "Net-(U5-B1)") (class "Default")
      (node (ref "U5") (pin "3") (pinfunction "B1_3") (pintype "passive"))
      (node (ref "U6") (pin "3") (pinfunction "B1_3") (pintype "passive"))
    )
    (net (code "70") (name "Net-(U7-AVDD18_XTAL)") (class "Default")
      (node (ref "C23") (pin "2") (pinfunction "2_2") (pintype "passive"))
      (node (ref "C24") (pin "2") (pinfunction "2_2") (pintype "passive"))
      (node (ref "FB3") (pin "1") (pinfunction "1_1") (pintype "passive"))
      (node (ref "U7") (pin "15") (pinfunction "AVDD18_XTAL_15") (pintype "passive"))
    )
    (net (code "71") (name "Net-(U7-GPIO3(LED2))") (class "Default")
      (node (ref "R22") (pin "1") (pinfunction "1_1") (pintype "passive"))
      (node (ref "U7") (pin "29") (pinfunction "GPIO3(LED2)_29") (pintype "passive"))
    )
    (net (code "72") (name "Net-(U7-GPIO8(WAKEUP_B))") (class "Default")
      (node (ref "R25") (pin "1") (pinfunction "1_1") (pintype "passive"))
      (node (ref "U7") (pin "33") (pinfunction "GPIO8(WAKEUP_B)_33") (pintype "passive"))
    )
    (net (code "73") (name "Net-(U7-GPIO10(SYNCE_LOCK))") (class "Default")
      (node (ref "R24") (pin "1") (pinfunction "1_1") (pintype "passive"))
      (node (ref "U7") (pin "19") (pinfunction "GPIO10(SYNCE_LOCK)_19") (pintype "passive"))
    )
    (net (code "74") (name "Net-(U7-MPXP)") (class "Default")
      (node (ref "R21") (pin "2") (pinfunction "2_2") (pintype "passive"))
      (node (ref "U7") (pin "9") (pinfunction "MPXP_9") (pintype "passive"))
    )
    (net (code "75") (name "Net-(U9-SW)") (class "Default")
      (node (ref "L1") (pin "1") (pinfunction "1_1") (pintype "passive"))
      (node (ref "U9") (pin "3") (pinfunction "SW_3") (pintype "passive"))
    )
    (net (code "76") (name "Net-(U10-SO)") (class "Default")
      (node (ref "R36") (pin "1") (pinfunction "1_1") (pintype "passive"))
      (node (ref "U10") (pin "2") (pinfunction "SO_2") (pintype "output"))
    )
    (net (code "77") (name "Net-(U10-~{HOLD})") (class "Default")
      (node (ref "R34") (pin "2") (pinfunction "2_2") (pintype "passive"))
      (node (ref "U10") (pin "7") (pinfunction "~{HOLD}_7") (pintype "input"))
    )
    (net (code "78") (name "Net-(U10-~{WP})") (class "Default")
      (node (ref "R35") (pin "2") (pinfunction "2_2") (pintype "passive"))
      (node (ref "U10") (pin "3") (pinfunction "~{WP}_3") (pintype "input"))
    )
    (net (code "79") (name "Net-(U11-SW)") (class "Default")
      (node (ref "L2") (pin "1") (pinfunction "1_1") (pintype "passive"))
      (node (ref "U11") (pin "3") (pinfunction "SW_3") (pintype "passive"))
    )
    (net (code "80") (name "Net-(U11-VO{slash}VFB)") (class "Default")
      (node (ref "R37") (pin "2") (pinfunction "2_2") (pintype "passive"))
      (node (ref "R38") (pin "1") (pinfunction "1_1") (pintype "passive"))
      (node (ref "U11") (pin "1") (pinfunction "VO/VFB_1") (pintype "bidirectional"))
    )
    (net (code "81") (name "VBUS_+5V") (class "Default")
      (node (ref "C1") (pin "2") (pinfunction "2_2") (pintype "passive"))
      (node (ref "C2") (pin "2") (pinfunction "2_2") (pintype "passive"))
      (node (ref "C20") (pin "2") (pinfunction "2_2") (pintype "passive"))
      (node (ref "C3") (pin "2") (pinfunction "2_2") (pintype "passive"))
      (node (ref "C35") (pin "2") (pinfunction "2_2") (pintype "passive"))
      (node (ref "C4") (pin "2") (pinfunction "2_2") (pintype "passive"))
      (node (ref "C5") (pin "2") (pinfunction "2_2") (pintype "passive"))
      (node (ref "C6") (pin "2") (pinfunction "2_2") (pintype "passive"))
      (node (ref "J3") (pin "2") (pinfunction "2_2") (pintype "passive"))
      (node (ref "J5") (pin "A4") (pinfunction "VBUS_A4") (pintype "passive"))
      (node (ref "J5") (pin "A9") (pinfunction "VBUS_A9") (pintype "passive"))
      (node (ref "J5") (pin "B4") (pinfunction "VBUS_B4") (pintype "passive"))
      (node (ref "J5") (pin "B9") (pinfunction "VBUS_B9") (pintype "passive"))
      (node (ref "R14") (pin "2") (pinfunction "2_2") (pintype "passive"))
      (node (ref "R2") (pin "2") (pinfunction "2_2") (pintype "passive"))
      (node (ref "R3") (pin "2") (pinfunction "2_2") (pintype "passive"))
      (node (ref "R4") (pin "2") (pinfunction "2_2") (pintype "passive"))
      (node (ref "R5") (pin "2") (pinfunction "2_2") (pintype "passive"))
      (node (ref "R6") (pin "2") (pinfunction "2_2") (pintype "passive"))
      (node (ref "R9") (pin "2") (pinfunction "2_2") (pintype "passive"))
      (node (ref "U1") (pin "8") (pinfunction "VCC_8") (pintype "passive"))
      (node (ref "U11") (pin "4") (pinfunction "VIN_SW_4") (pintype "input"))
      (node (ref "U11") (pin "5") (pinfunction "VIN_A_5") (pintype "input"))
      (node (ref "U11") (pin "6") (pinfunction "VINH_6") (pintype "input"))
      (node (ref "U2") (pin "5") (pinfunction "VCC_5") (pintype "passive"))
      (node (ref "U3") (pin "5") (pinfunction "VCC_5") (pintype "passive"))
      (node (ref "U4") (pin "8") (pinfunction "VCC_8") (pintype "passive"))
      (node (ref "U5") (pin "5") (pinfunction "VCC_5") (pintype "passive"))
      (node (ref "U6") (pin "5") (pinfunction "VCC_5") (pintype "passive"))
      (node (ref "U8") (pin "3") (pinfunction "VBUS/GND_3") (pintype "power_in"))
      (node (ref "U9") (pin "4") (pinfunction "VIN_SW_4") (pintype "input"))
      (node (ref "U9") (pin "5") (pinfunction "VIN_A_5") (pintype "input"))
      (node (ref "U9") (pin "6") (pinfunction "VINH_6") (pintype "input"))
    )
    (net (code "82") (name "VCCK10") (class "Default")
      (node (ref "C34") (pin "2") (pinfunction "2_2") (pintype "passive"))
      (node (ref "C41") (pin "2") (pinfunction "2_2") (pintype "passive"))
      (node (ref "C42") (pin "2") (pinfunction "2_2") (pintype "passive"))
      (node (ref "C43") (pin "2") (pinfunction "2_2") (pintype "passive"))
      (node (ref "C44") (pin "2") (pinfunction "2_2") (pintype "passive"))
      (node (ref "L2") (pin "2") (pinfunction "2_2") (pintype "passive"))
      (node (ref "R37") (pin "1") (pinfunction "1_1") (pintype "passive"))
      (node (ref "U7") (pin "24") (pinfunction "VCCK_24") (pintype "passive"))
      (node (ref "U7") (pin "30") (pinfunction "VCCK_30") (pintype "passive"))
      (node (ref "U7") (pin "31") (pinfunction "VCCK_31") (pintype "passive"))
      (node (ref "U7") (pin "32") (pinfunction "VCCK_32") (pintype "passive"))
      (node (ref "U7") (pin "57") (pinfunction "VCCK_57") (pintype "passive"))
      (node (ref "U7") (pin "58") (pinfunction "VCCK_58") (pintype "passive"))
    )
    (net (code "83") (name "unconnected-(IC1-EXTINT-Pad5)") (class "Default")
      (node (ref "IC1") (pin "5") (pinfunction "EXTINT_5") (pintype "passive+no_connect"))
    )
    (net (code "84") (name "unconnected-(IC1-LNA_EN-Pad13)") (class "Default")
      (node (ref "IC1") (pin "13") (pinfunction "LNA_EN_13") (pintype "passive+no_connect"))
    )
    (net (code "85") (name "unconnected-(IC1-RESET_N-Pad9)") (class "Default")
      (node (ref "IC1") (pin "9") (pinfunction "RESET_N_9") (pintype "passive+no_connect"))
    )
    (net (code "86") (name "unconnected-(IC1-VIO_SEL-Pad15)") (class "Default")
      (node (ref "IC1") (pin "15") (pinfunction "VIO_SEL_15") (pintype "passive+no_connect"))
    )
    (net (code "87") (name "unconnected-(IC1-V_BCKP-Pad6)") (class "Default")
      (node (ref "IC1") (pin "6") (pinfunction "V_BCKP_6") (pintype "passive+no_connect"))
    )
    (net (code "88") (name "unconnected-(IC2-EXTINT-Pad4)") (class "Default")
      (node (ref "IC2") (pin "4") (pinfunction "EXTINT_4") (pintype "passive+no_connect"))
    )
    (net (code "89") (name "unconnected-(IC2-LNA_EN-Pad14)") (class "Default")
      (node (ref "IC2") (pin "14") (pinfunction "LNA_EN_14") (pintype "passive+no_connect"))
    )
    (net (code "90") (name "unconnected-(IC2-RESERVED_1-Pad15)") (class "Default")
      (node (ref "IC2") (pin "15") (pinfunction "RESERVED_1_15") (pintype "passive+no_connect"))
    )
    (net (code "91") (name "unconnected-(IC2-RESERVED_2-Pad16)") (class "Default")
      (node (ref "IC2") (pin "16") (pinfunction "RESERVED_2_16") (pintype "passive+no_connect"))
    )
    (net (code "92") (name "unconnected-(IC2-RESERVED_3-Pad17)") (class "Default")
      (node (ref "IC2") (pin "17") (pinfunction "RESERVED_3_17") (pintype "passive+no_connect"))
    )
    (net (code "93") (name "unconnected-(IC2-RESET_N-Pad8)") (class "Default")
      (node (ref "IC2") (pin "8") (pinfunction "RESET_N_8") (pintype "passive+no_connect"))
    )
    (net (code "94") (name "unconnected-(IC2-USB_DM-Pad5)") (class "Default")
      (node (ref "IC2") (pin "5") (pinfunction "USB_DM_5") (pintype "passive+no_connect"))
    )
    (net (code "95") (name "unconnected-(IC2-USB_DP-Pad6)") (class "Default")
      (node (ref "IC2") (pin "6") (pinfunction "USB_DP_6") (pintype "passive+no_connect"))
    )
    (net (code "96") (name "unconnected-(IC2-V_BCKP-Pad22)") (class "Default")
      (node (ref "IC2") (pin "22") (pinfunction "V_BCKP_22") (pintype "passive+no_connect"))
    )
    (net (code "97") (name "unconnected-(J4-VCC-PadP9)") (class "Default")
      (node (ref "J4") (pin "P9") (pinfunction "VCC_P9") (pintype "passive+no_connect"))
    )
    (net (code "98") (name "unconnected-(J5-SBU1-PadA8)") (class "Default")
      (node (ref "J5") (pin "A8") (pinfunction "SBU1_A8") (pintype "passive+no_connect"))
    )
    (net (code "99") (name "unconnected-(J5-SBU2-PadB8)") (class "Default")
      (node (ref "J5") (pin "B8") (pinfunction "SBU2_B8") (pintype "passive+no_connect"))
    )
    (net (code "100") (name "unconnected-(U7-CKO-Pad18)") (class "Default")
      (node (ref "U7") (pin "18") (pinfunction "CKO_18") (pintype "passive+no_connect"))
    )
    (net (code "101") (name "unconnected-(U7-GPIO0(MDC)-Pad48)") (class "Default")
      (node (ref "U7") (pin "48") (pinfunction "GPIO0(MDC)_48") (pintype "passive+no_connect"))
    )
    (net (code "102") (name "unconnected-(U7-GPIO1(MDIO)-Pad49)") (class "Default")
      (node (ref "U7") (pin "49") (pinfunction "GPIO1(MDIO)_49") (pintype "passive+no_connect"))
    )
    (net (code "103") (name "unconnected-(U7-GPIO2-Pad22)") (class "Default")
      (node (ref "U7") (pin "22") (pinfunction "GPIO2_22") (pintype "passive+no_connect"))
    )
    (net (code "104") (name "unconnected-(U7-GPIO15(1588_TOD)-Pad47)") (class "Default")
      (node (ref "U7") (pin "47") (pinfunction "GPIO15(1588_TOD)_47") (pintype "passive+no_connect"))
    )
    (net (code "105") (name "unconnected-(U7-LX-Pad60)") (class "Default")
      (node (ref "U7") (pin "60") (pinfunction "LX_60") (pintype "passive+no_connect"))
    )
    (net (code "106") (name "unconnected-(U8-NC-Pad9)") (class "Default")
      (node (ref "U8") (pin "9") (pinfunction "NC_9") (pintype "passive+no_connect"))
    )
    (net (code "107") (name "unconnected-(U8-NC-Pad10)") (class "Default")
      (node (ref "U8") (pin "10") (pinfunction "NC_10") (pintype "passive+no_connect"))
    )
  )
)
